# frames_v03.net
KiCad netlist of a schematic drawn in EAGLE
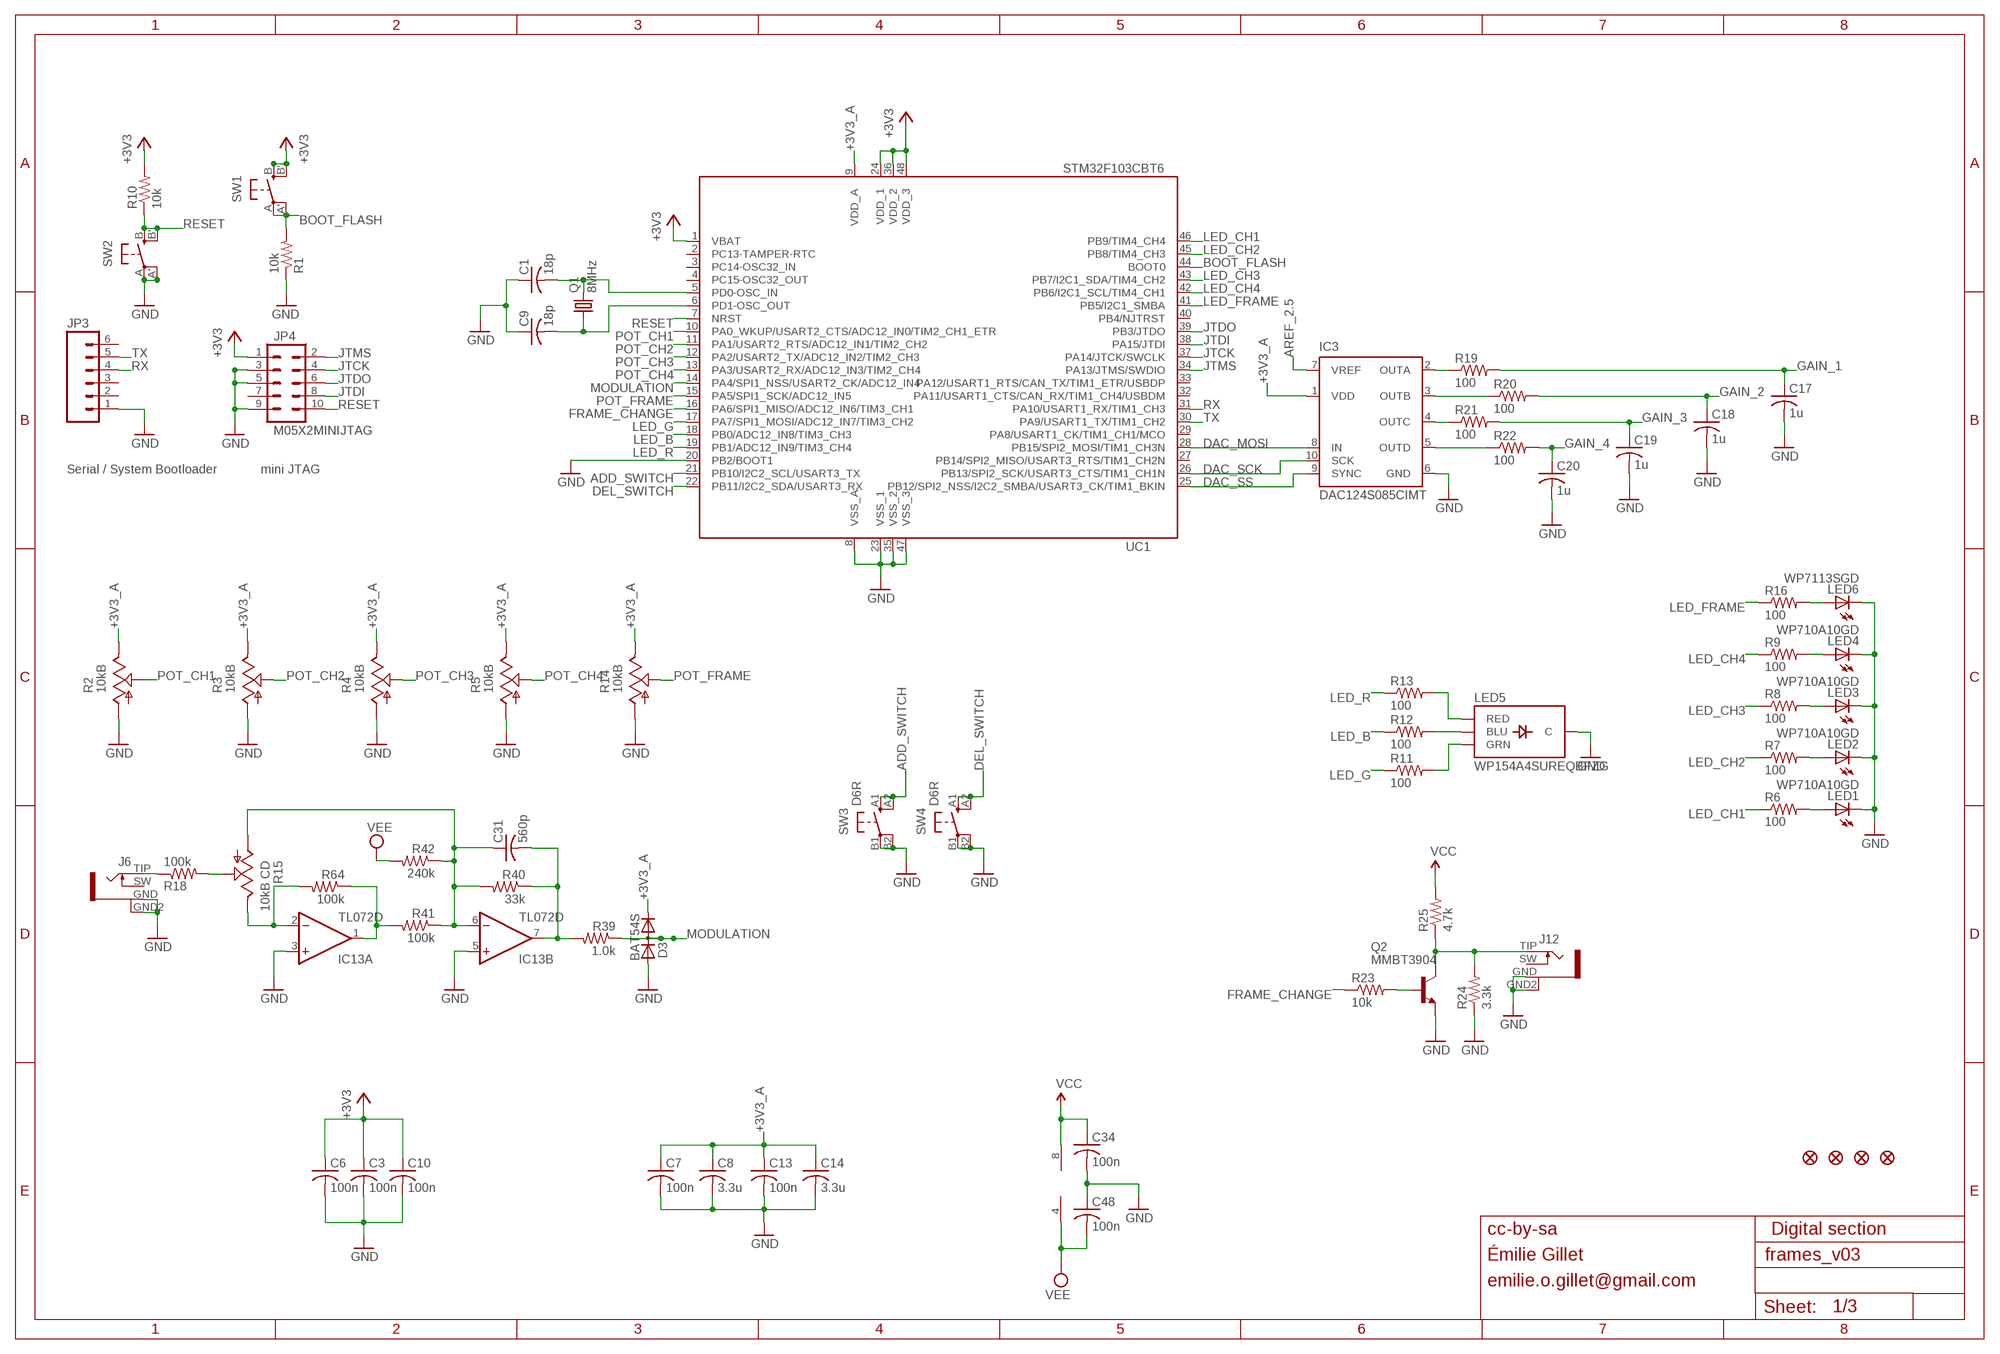
[diagram p0: schematic, sheet 1]
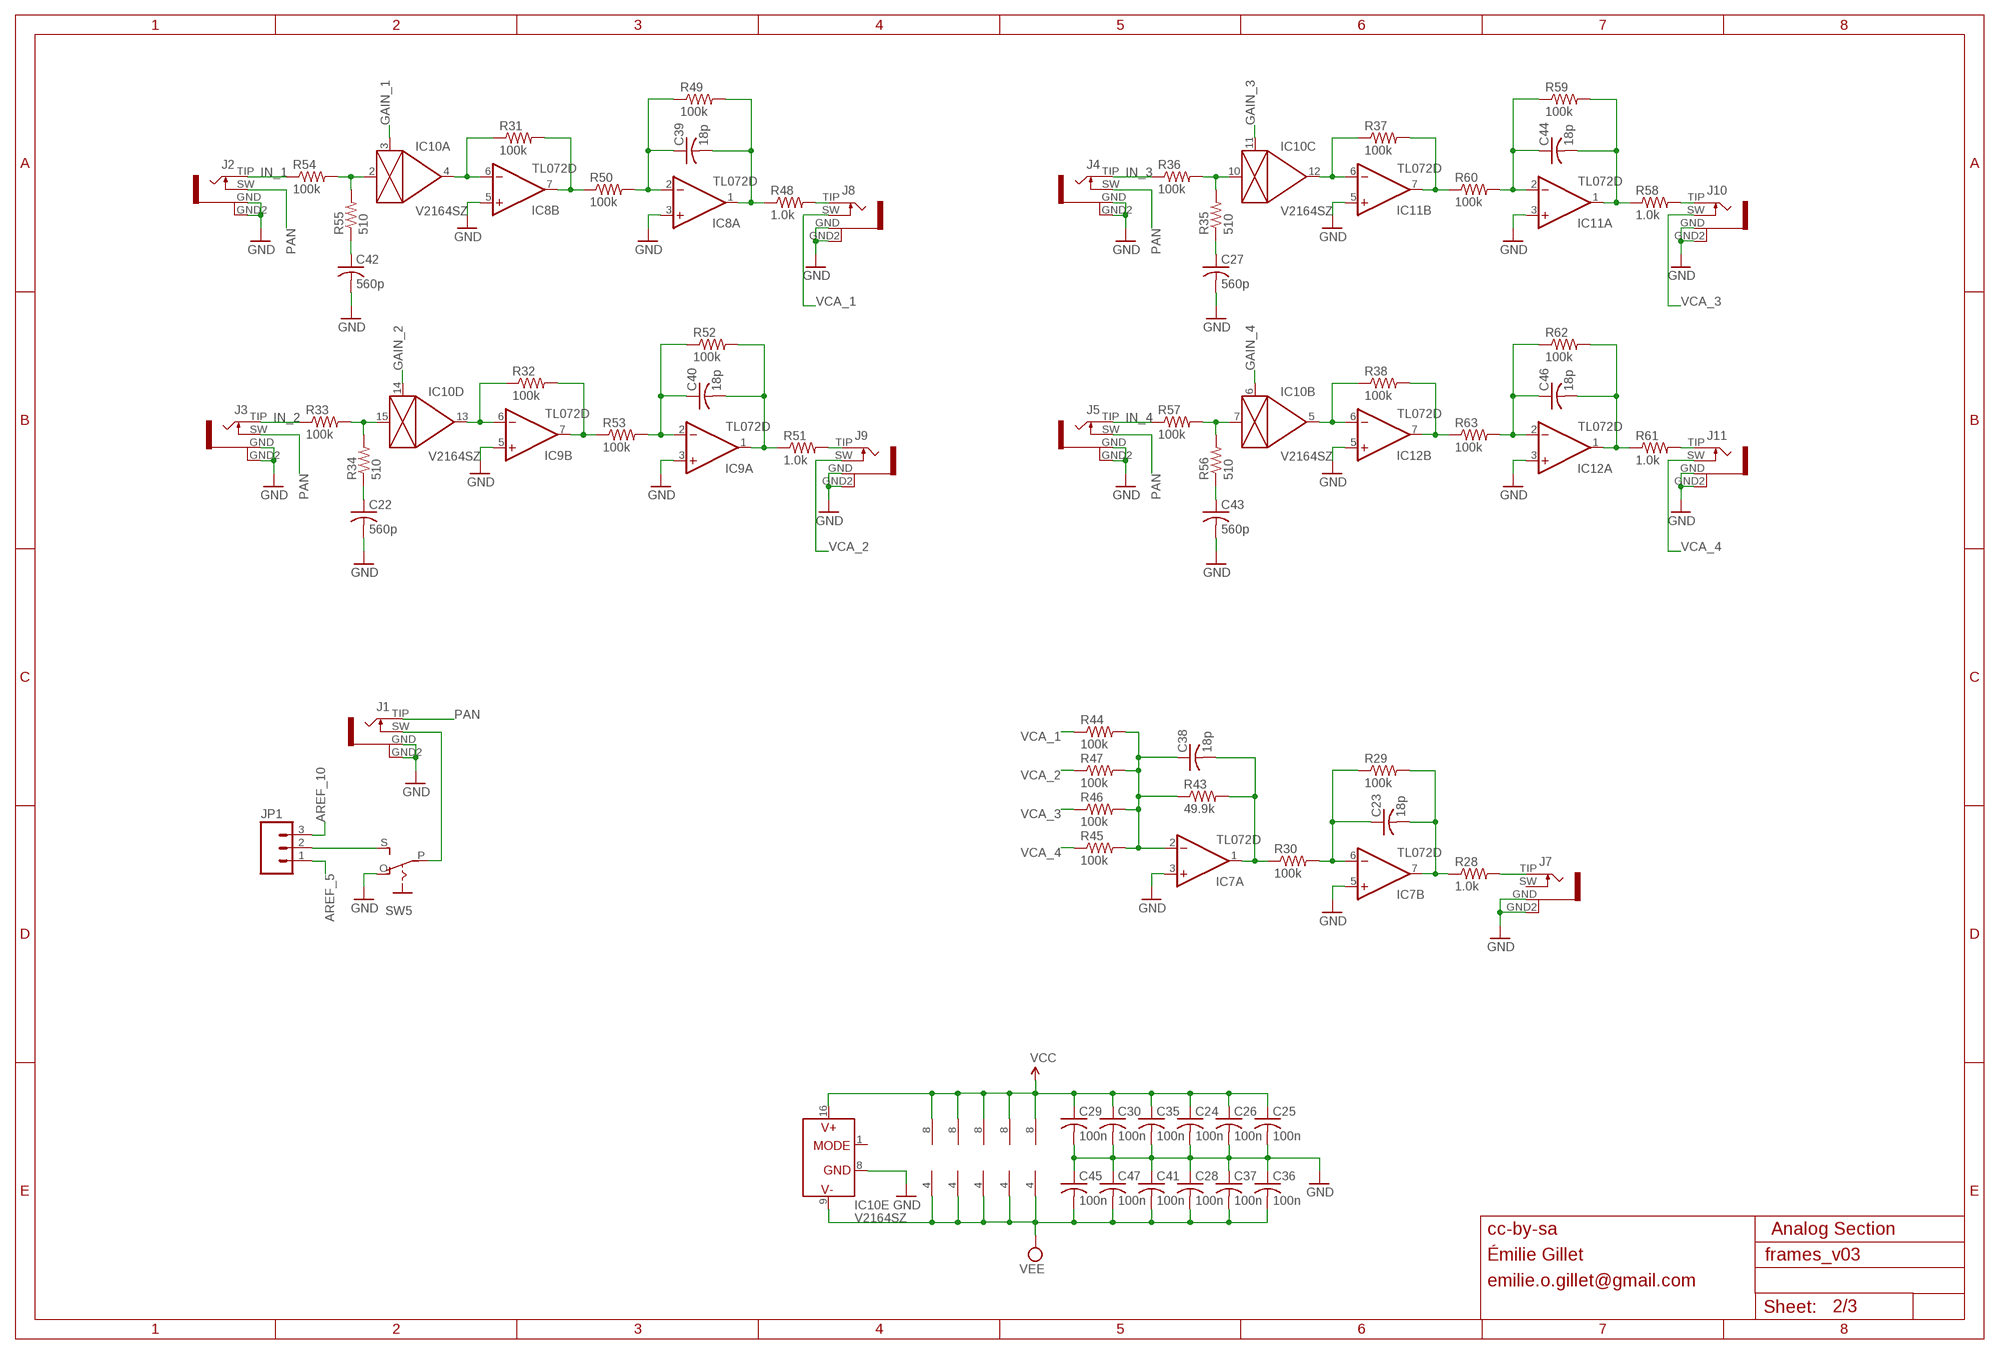
[diagram p1: schematic, sheet 2]
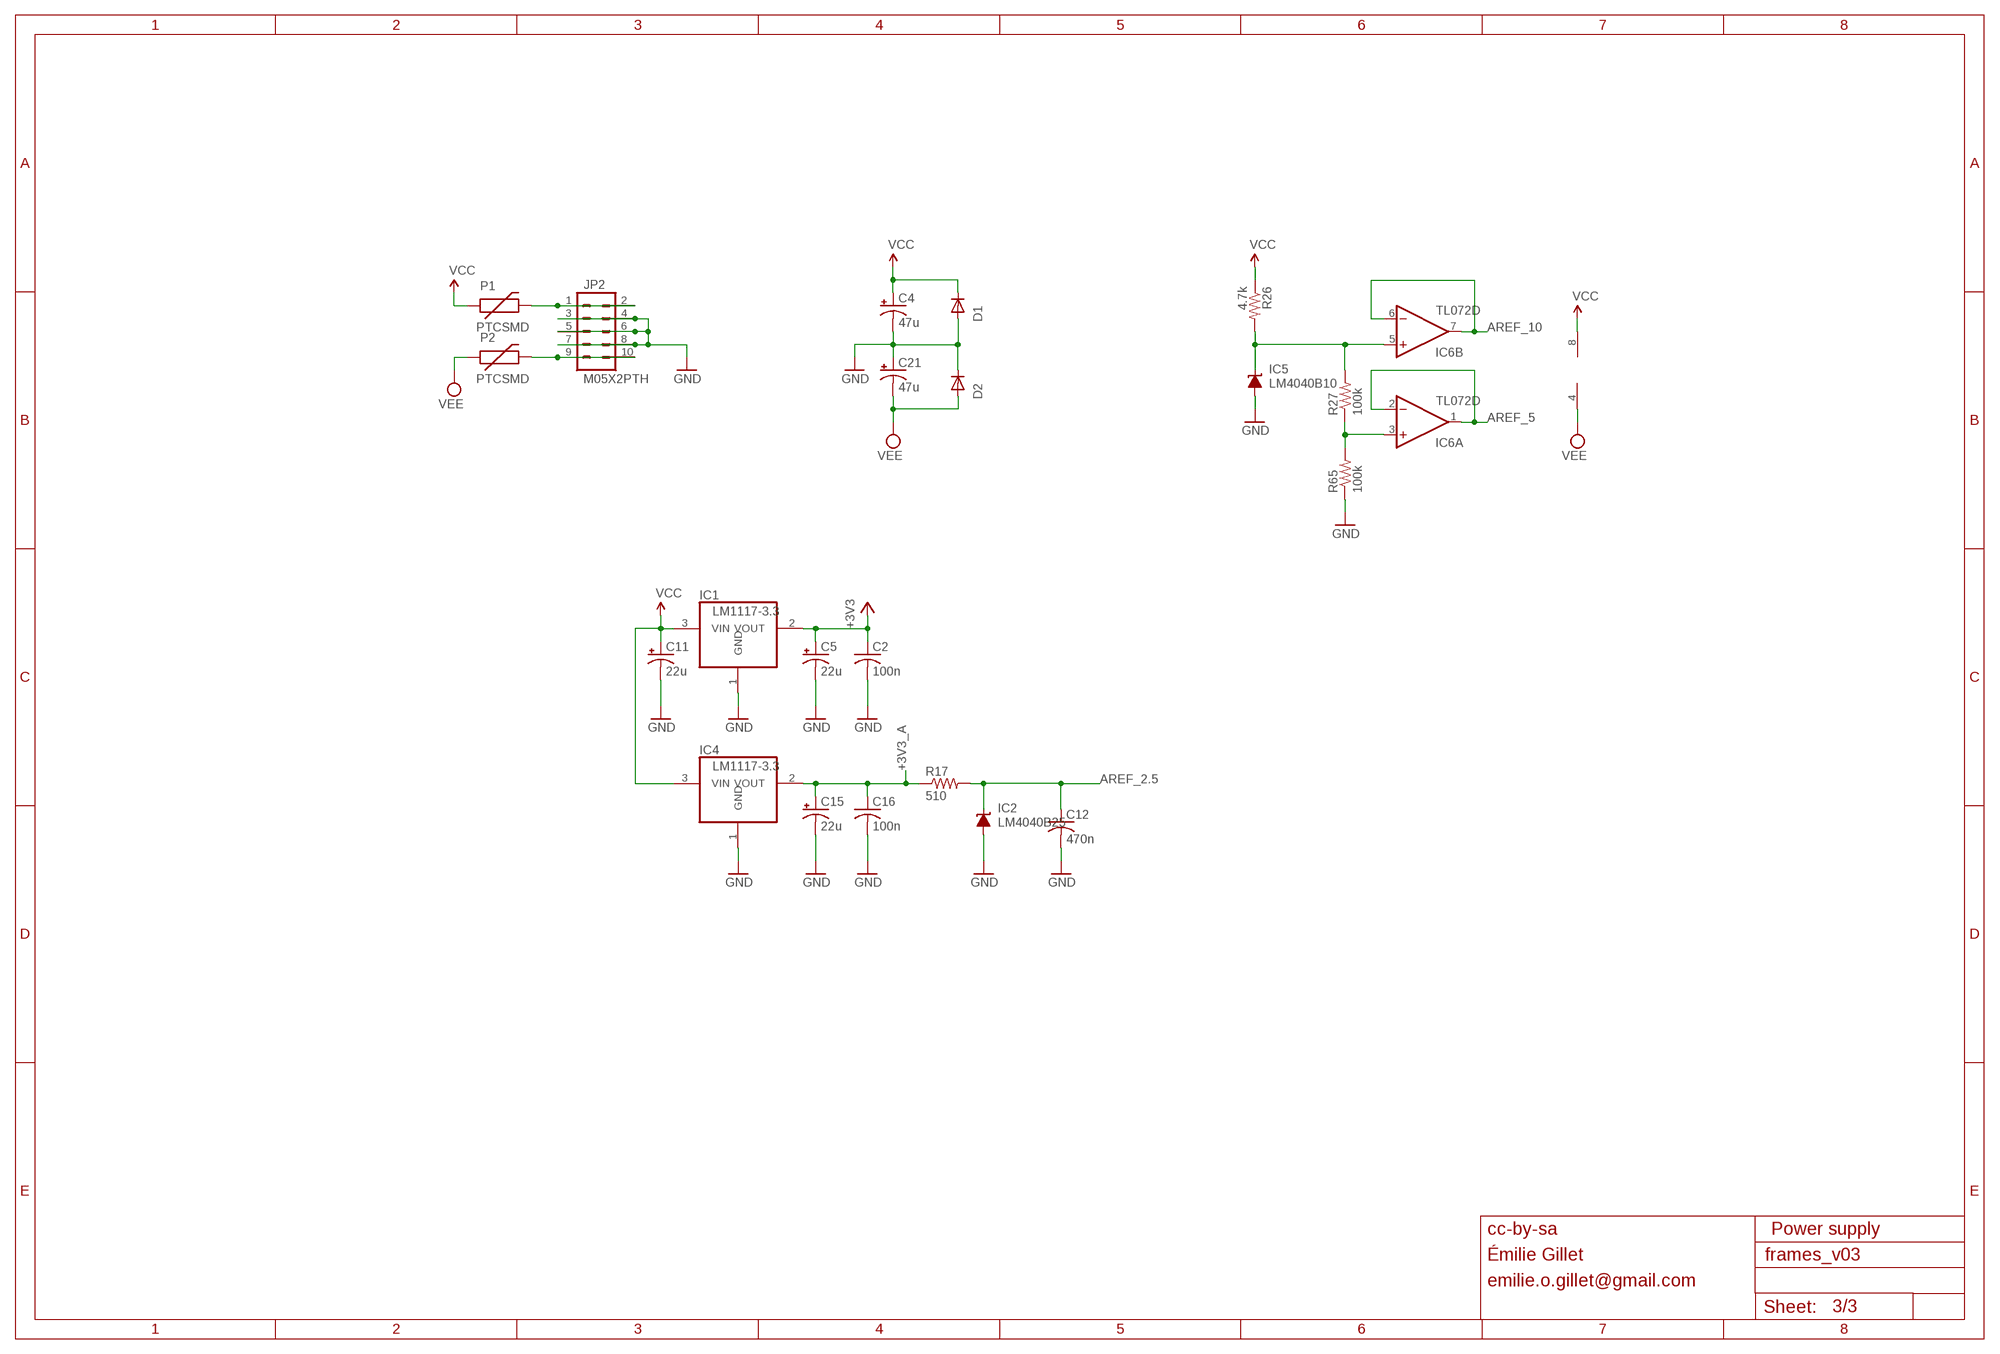
[diagram p2: schematic, sheet 3]

(export (version "E")
  (design (tool "Eeschema 10.0.6"))
  (components
    (comp (ref "C1")
      (value "18p")
      (footprint "eagle-import:C0603")
      (libsource (lib "eagle-import") (part "C-USC0603"))
    )
    (comp (ref "C3")
      (value "100n")
      (footprint "eagle-import:C0603")
      (libsource (lib "eagle-import") (part "C-USC0603"))
    )
    (comp (ref "C6")
      (value "100n")
      (footprint "eagle-import:C0603")
      (libsource (lib "eagle-import") (part "C-USC0603"))
    )
    (comp (ref "C7")
      (value "100n")
      (footprint "eagle-import:C0603")
      (libsource (lib "eagle-import") (part "C-USC0603"))
    )
    (comp (ref "C8")
      (value "3.3u")
      (footprint "eagle-import:C0603")
      (libsource (lib "eagle-import") (part "C-USC0603"))
    )
    (comp (ref "C9")
      (value "18p")
      (footprint "eagle-import:C0603")
      (libsource (lib "eagle-import") (part "C-USC0603"))
    )
    (comp (ref "C10")
      (value "100n")
      (footprint "eagle-import:C0603")
      (libsource (lib "eagle-import") (part "C-USC0603"))
    )
    (comp (ref "C13")
      (value "100n")
      (footprint "eagle-import:C0603")
      (libsource (lib "eagle-import") (part "C-USC0603"))
    )
    (comp (ref "C14")
      (value "3.3u")
      (footprint "eagle-import:C0603")
      (libsource (lib "eagle-import") (part "C-USC0603"))
    )
    (comp (ref "C17")
      (value "1u")
      (footprint "eagle-import:C0603")
      (libsource (lib "eagle-import") (part "C-USC0603"))
    )
    (comp (ref "C18")
      (value "1u")
      (footprint "eagle-import:C0603")
      (libsource (lib "eagle-import") (part "C-USC0603"))
    )
    (comp (ref "C19")
      (value "1u")
      (footprint "eagle-import:C0603")
      (libsource (lib "eagle-import") (part "C-USC0603"))
    )
    (comp (ref "C20")
      (value "1u")
      (footprint "eagle-import:C0603")
      (libsource (lib "eagle-import") (part "C-USC0603"))
    )
    (comp (ref "C31")
      (value "560p")
      (footprint "eagle-import:C0603")
      (libsource (lib "eagle-import") (part "C-USC0603"))
    )
    (comp (ref "C34")
      (value "100n")
      (footprint "eagle-import:C0603")
      (libsource (lib "eagle-import") (part "C-USC0603"))
    )
    (comp (ref "C48")
      (value "100n")
      (footprint "eagle-import:C0603")
      (libsource (lib "eagle-import") (part "C-USC0603"))
    )
    (comp (ref "D3")
      (value "BAT54S")
      (footprint "eagle-import:SOT23")
      (libsource (lib "eagle-import") (part "DIODE_2CACA-SOT23"))
    )
    (comp (ref "F1")
      (value "FIDUCIAL1X2")
      (footprint "eagle-import:FIDUCIAL-1X2")
      (libsource (lib "eagle-import") (part "FIDUCIAL1X2"))
    )
    (comp (ref "F2")
      (value "FIDUCIAL1X2")
      (footprint "eagle-import:FIDUCIAL-1X2")
      (libsource (lib "eagle-import") (part "FIDUCIAL1X2"))
    )
    (comp (ref "F3")
      (value "FIDUCIAL1X2")
      (footprint "eagle-import:FIDUCIAL-1X2")
      (libsource (lib "eagle-import") (part "FIDUCIAL1X2"))
    )
    (comp (ref "F4")
      (value "FIDUCIAL1X2")
      (footprint "eagle-import:FIDUCIAL-1X2")
      (libsource (lib "eagle-import") (part "FIDUCIAL1X2"))
    )
    (comp (ref "IC3")
      (value "DAC124S085CIMT")
      (footprint "eagle-import:MSOP10")
      (libsource (lib "eagle-import") (part "DAC124S085CIMT"))
    )
    (comp (ref "IC13")
      (value "TL072D")
      (footprint "eagle-import:SO08")
      (libsource (lib "eagle-import") (part "og-linear_TL072D"))
    )
    (comp (ref "J6")
      (value "PJ301WQP")
      (footprint "eagle-import:WQP_PJ_301BM")
      (libsource (lib "eagle-import") (part "PJ301WQP"))
    )
    (comp (ref "J12")
      (value "PJ301WQP")
      (footprint "eagle-import:WQP_PJ_301BM")
      (libsource (lib "eagle-import") (part "PJ301WQP"))
    )
    (comp (ref "JP3")
      (value "M06SIP")
      (footprint "eagle-import:1X06")
      (libsource (lib "eagle-import") (part "M06SIP"))
    )
    (comp (ref "JP4")
      (value "M05X2MINIJTAG")
      (footprint "eagle-import:2X5-1.27")
      (libsource (lib "eagle-import") (part "M05X2MINIJTAG"))
    )
    (comp (ref "LED1")
      (value "WP710A10GD")
      (footprint "eagle-import:LED3MM")
      (libsource (lib "eagle-import") (part "LED3MM"))
    )
    (comp (ref "LED2")
      (value "WP710A10GD")
      (footprint "eagle-import:LED3MM")
      (libsource (lib "eagle-import") (part "LED3MM"))
    )
    (comp (ref "LED3")
      (value "WP710A10GD")
      (footprint "eagle-import:LED3MM")
      (libsource (lib "eagle-import") (part "LED3MM"))
    )
    (comp (ref "LED4")
      (value "WP710A10GD")
      (footprint "eagle-import:LED3MM")
      (libsource (lib "eagle-import") (part "LED3MM"))
    )
    (comp (ref "LED5")
      (value "WP154A4SUREQBFZG")
      (footprint "eagle-import:LED-TRICOLOR-THROUGHHOLE")
      (libsource (lib "eagle-import") (part "LED-TRICOLOR-THROUGHHOLE"))
    )
    (comp (ref "LED6")
      (value "WP7113SGD")
      (footprint "eagle-import:LED5MM")
      (libsource (lib "eagle-import") (part "LED5MM"))
    )
    (comp (ref "Q1")
      (value "8MHz")
      (footprint "eagle-import:HC49UP")
      (libsource (lib "eagle-import") (part "CRYSTALHC49UP"))
    )
    (comp (ref "Q2")
      (value "MMBT3904")
      (footprint "eagle-import:SOT23-BEC")
      (libsource (lib "eagle-import") (part "-NPN-SOT23-BECMMBT3904LT1"))
    )
    (comp (ref "R1")
      (value "10k")
      (footprint "eagle-import:R0603")
      (libsource (lib "eagle-import") (part "R-US_R0603"))
    )
    (comp (ref "R2")
      (value "10kB")
      (footprint "eagle-import:ALPS_POT_VERTICAL_PS")
      (libsource (lib "eagle-import") (part "POT_USVERTICAL_PS"))
    )
    (comp (ref "R3")
      (value "10kB")
      (footprint "eagle-import:ALPS_POT_VERTICAL_PS")
      (libsource (lib "eagle-import") (part "POT_USVERTICAL_PS"))
    )
    (comp (ref "R4")
      (value "10kB")
      (footprint "eagle-import:ALPS_POT_VERTICAL_PS")
      (libsource (lib "eagle-import") (part "POT_USVERTICAL_PS"))
    )
    (comp (ref "R5")
      (value "10kB")
      (footprint "eagle-import:ALPS_POT_VERTICAL_PS")
      (libsource (lib "eagle-import") (part "POT_USVERTICAL_PS"))
    )
    (comp (ref "R6")
      (value "100")
      (footprint "eagle-import:R0603")
      (libsource (lib "eagle-import") (part "R-US_R0603"))
    )
    (comp (ref "R7")
      (value "100")
      (footprint "eagle-import:R0603")
      (libsource (lib "eagle-import") (part "R-US_R0603"))
    )
    (comp (ref "R8")
      (value "100")
      (footprint "eagle-import:R0603")
      (libsource (lib "eagle-import") (part "R-US_R0603"))
    )
    (comp (ref "R9")
      (value "100")
      (footprint "eagle-import:R0603")
      (libsource (lib "eagle-import") (part "R-US_R0603"))
    )
    (comp (ref "R10")
      (value "10k")
      (footprint "eagle-import:R0603")
      (libsource (lib "eagle-import") (part "R-US_R0603"))
    )
    (comp (ref "R11")
      (value "100")
      (footprint "eagle-import:R0603")
      (libsource (lib "eagle-import") (part "R-US_R0603"))
    )
    (comp (ref "R12")
      (value "100")
      (footprint "eagle-import:R0603")
      (libsource (lib "eagle-import") (part "R-US_R0603"))
    )
    (comp (ref "R13")
      (value "100")
      (footprint "eagle-import:R0603")
      (libsource (lib "eagle-import") (part "R-US_R0603"))
    )
    (comp (ref "R14")
      (value "10kB")
      (footprint "eagle-import:ALPS_POT_VERTICAL_PS")
      (libsource (lib "eagle-import") (part "POT_USVERTICAL_PS"))
    )
    (comp (ref "R15")
      (value "10kB CD")
      (footprint "eagle-import:ALPS_POT_VERTICAL_PS")
      (libsource (lib "eagle-import") (part "POT_USVERTICAL_PS"))
    )
    (comp (ref "R16")
      (value "100")
      (footprint "eagle-import:R0603")
      (libsource (lib "eagle-import") (part "R-US_R0603"))
    )
    (comp (ref "R18")
      (value "100k")
      (footprint "eagle-import:R0603")
      (libsource (lib "eagle-import") (part "R-US_R0603"))
    )
    (comp (ref "R19")
      (value "100")
      (footprint "eagle-import:R0603")
      (libsource (lib "eagle-import") (part "R-US_R0603"))
    )
    (comp (ref "R20")
      (value "100")
      (footprint "eagle-import:R0603")
      (libsource (lib "eagle-import") (part "R-US_R0603"))
    )
    (comp (ref "R21")
      (value "100")
      (footprint "eagle-import:R0603")
      (libsource (lib "eagle-import") (part "R-US_R0603"))
    )
    (comp (ref "R22")
      (value "100")
      (footprint "eagle-import:R0603")
      (libsource (lib "eagle-import") (part "R-US_R0603"))
    )
    (comp (ref "R23")
      (value "10k")
      (footprint "eagle-import:R0603")
      (libsource (lib "eagle-import") (part "R-US_R0603"))
    )
    (comp (ref "R24")
      (value "3.3k")
      (footprint "eagle-import:R0603")
      (libsource (lib "eagle-import") (part "R-US_R0603"))
    )
    (comp (ref "R25")
      (value "4.7k")
      (footprint "eagle-import:R0603")
      (libsource (lib "eagle-import") (part "R-US_R0603"))
    )
    (comp (ref "R39")
      (value "1.0k")
      (footprint "eagle-import:R0603")
      (libsource (lib "eagle-import") (part "R-US_R0603"))
    )
    (comp (ref "R40")
      (value "33k")
      (footprint "eagle-import:R0603")
      (libsource (lib "eagle-import") (part "R-US_R0603"))
    )
    (comp (ref "R41")
      (value "100k")
      (footprint "eagle-import:R0603")
      (libsource (lib "eagle-import") (part "R-US_R0603"))
    )
    (comp (ref "R42")
      (value "240k")
      (footprint "eagle-import:R0603")
      (libsource (lib "eagle-import") (part "R-US_R0603"))
    )
    (comp (ref "R64")
      (value "100k")
      (footprint "eagle-import:R0603")
      (libsource (lib "eagle-import") (part "R-US_R0603"))
    )
    (comp (ref "SW1")
      (value "EVQQ2")
      (footprint "eagle-import:EVQ-Q2")
      (libsource (lib "eagle-import") (part "EVQQ2"))
    )
    (comp (ref "SW2")
      (value "EVQQ2")
      (footprint "eagle-import:EVQ-Q2")
      (libsource (lib "eagle-import") (part "EVQQ2"))
    )
    (comp (ref "SW3")
      (value "D6R")
      (footprint "eagle-import:D6R")
      (libsource (lib "eagle-import") (part "D6R"))
    )
    (comp (ref "SW4")
      (value "D6R")
      (footprint "eagle-import:D6R")
      (libsource (lib "eagle-import") (part "D6R"))
    )
    (comp (ref "UC1")
      (value "STM32F103CBT6")
      (footprint "eagle-import:LQFP48")
      (libsource (lib "eagle-import") (part "STM32F103CB"))
    )
    (comp (ref "C22")
      (value "560p")
      (footprint "eagle-import:C0603")
      (libsource (lib "eagle-import") (part "C-USC0603"))
    )
    (comp (ref "C23")
      (value "18p")
      (footprint "eagle-import:C0603")
      (libsource (lib "eagle-import") (part "C-USC0603"))
    )
    (comp (ref "C24")
      (value "100n")
      (footprint "eagle-import:C0603")
      (libsource (lib "eagle-import") (part "C-USC0603"))
    )
    (comp (ref "C25")
      (value "100n")
      (footprint "eagle-import:C0603")
      (libsource (lib "eagle-import") (part "C-USC0603"))
    )
    (comp (ref "C26")
      (value "100n")
      (footprint "eagle-import:C0603")
      (libsource (lib "eagle-import") (part "C-USC0603"))
    )
    (comp (ref "C27")
      (value "560p")
      (footprint "eagle-import:C0603")
      (libsource (lib "eagle-import") (part "C-USC0603"))
    )
    (comp (ref "C28")
      (value "100n")
      (footprint "eagle-import:C0603")
      (libsource (lib "eagle-import") (part "C-USC0603"))
    )
    (comp (ref "C29")
      (value "100n")
      (footprint "eagle-import:C0603")
      (libsource (lib "eagle-import") (part "C-USC0603"))
    )
    (comp (ref "C30")
      (value "100n")
      (footprint "eagle-import:C0603")
      (libsource (lib "eagle-import") (part "C-USC0603"))
    )
    (comp (ref "C35")
      (value "100n")
      (footprint "eagle-import:C0603")
      (libsource (lib "eagle-import") (part "C-USC0603"))
    )
    (comp (ref "C36")
      (value "100n")
      (footprint "eagle-import:C0603")
      (libsource (lib "eagle-import") (part "C-USC0603"))
    )
    (comp (ref "C37")
      (value "100n")
      (footprint "eagle-import:C0603")
      (libsource (lib "eagle-import") (part "C-USC0603"))
    )
    (comp (ref "C38")
      (value "18p")
      (footprint "eagle-import:C0603")
      (libsource (lib "eagle-import") (part "C-USC0603"))
    )
    (comp (ref "C39")
      (value "18p")
      (footprint "eagle-import:C0603")
      (libsource (lib "eagle-import") (part "C-USC0603"))
    )
    (comp (ref "C40")
      (value "18p")
      (footprint "eagle-import:C0603")
      (libsource (lib "eagle-import") (part "C-USC0603"))
    )
    (comp (ref "C41")
      (value "100n")
      (footprint "eagle-import:C0603")
      (libsource (lib "eagle-import") (part "C-USC0603"))
    )
    (comp (ref "C42")
      (value "560p")
      (footprint "eagle-import:C0603")
      (libsource (lib "eagle-import") (part "C-USC0603"))
    )
    (comp (ref "C43")
      (value "560p")
      (footprint "eagle-import:C0603")
      (libsource (lib "eagle-import") (part "C-USC0603"))
    )
    (comp (ref "C44")
      (value "18p")
      (footprint "eagle-import:C0603")
      (libsource (lib "eagle-import") (part "C-USC0603"))
    )
    (comp (ref "C45")
      (value "100n")
      (footprint "eagle-import:C0603")
      (libsource (lib "eagle-import") (part "C-USC0603"))
    )
    (comp (ref "C46")
      (value "18p")
      (footprint "eagle-import:C0603")
      (libsource (lib "eagle-import") (part "C-USC0603"))
    )
    (comp (ref "C47")
      (value "100n")
      (footprint "eagle-import:C0603")
      (libsource (lib "eagle-import") (part "C-USC0603"))
    )
    (comp (ref "IC7")
      (value "TL072D")
      (footprint "eagle-import:SO08")
      (libsource (lib "eagle-import") (part "og-linear_TL072D"))
    )
    (comp (ref "IC8")
      (value "TL072D")
      (footprint "eagle-import:SO08")
      (libsource (lib "eagle-import") (part "og-linear_TL072D"))
    )
    (comp (ref "IC9")
      (value "TL072D")
      (footprint "eagle-import:SO08")
      (libsource (lib "eagle-import") (part "og-linear_TL072D"))
    )
    (comp (ref "IC10")
      (value "V2164SZ")
      (footprint "eagle-import:SOIC16N")
      (libsource (lib "eagle-import") (part "SSM2164S"))
    )
    (comp (ref "IC11")
      (value "TL072D")
      (footprint "eagle-import:SO08")
      (libsource (lib "eagle-import") (part "og-linear_TL072D"))
    )
    (comp (ref "IC12")
      (value "TL072D")
      (footprint "eagle-import:SO08")
      (libsource (lib "eagle-import") (part "og-linear_TL072D"))
    )
    (comp (ref "J1")
      (value "PJ301WQP")
      (footprint "eagle-import:WQP_PJ_301BM")
      (libsource (lib "eagle-import") (part "PJ301WQP"))
    )
    (comp (ref "J2")
      (value "PJ301WQP")
      (footprint "eagle-import:WQP_PJ_301BM")
      (libsource (lib "eagle-import") (part "PJ301WQP"))
    )
    (comp (ref "J3")
      (value "PJ301WQP")
      (footprint "eagle-import:WQP_PJ_301BM")
      (libsource (lib "eagle-import") (part "PJ301WQP"))
    )
    (comp (ref "J4")
      (value "PJ301WQP")
      (footprint "eagle-import:WQP_PJ_301BM")
      (libsource (lib "eagle-import") (part "PJ301WQP"))
    )
    (comp (ref "J5")
      (value "PJ301WQP")
      (footprint "eagle-import:WQP_PJ_301BM")
      (libsource (lib "eagle-import") (part "PJ301WQP"))
    )
    (comp (ref "J7")
      (value "PJ301WQP")
      (footprint "eagle-import:WQP_PJ_301BM")
      (libsource (lib "eagle-import") (part "PJ301WQP"))
    )
    (comp (ref "J8")
      (value "PJ301WQP")
      (footprint "eagle-import:WQP_PJ_301BM")
      (libsource (lib "eagle-import") (part "PJ301WQP"))
    )
    (comp (ref "J9")
      (value "PJ301WQP")
      (footprint "eagle-import:WQP_PJ_301BM")
      (libsource (lib "eagle-import") (part "PJ301WQP"))
    )
    (comp (ref "J10")
      (value "PJ301WQP")
      (footprint "eagle-import:WQP_PJ_301BM")
      (libsource (lib "eagle-import") (part "PJ301WQP"))
    )
    (comp (ref "J11")
      (value "PJ301WQP")
      (footprint "eagle-import:WQP_PJ_301BM")
      (libsource (lib "eagle-import") (part "PJ301WQP"))
    )
    (comp (ref "JP1")
      (value "M03PTH")
      (footprint "eagle-import:1X03")
      (libsource (lib "eagle-import") (part "M03PTH"))
    )
    (comp (ref "R28")
      (value "1.0k")
      (footprint "eagle-import:R0603")
      (libsource (lib "eagle-import") (part "R-US_R0603"))
    )
    (comp (ref "R29")
      (value "100k")
      (footprint "eagle-import:R0603")
      (libsource (lib "eagle-import") (part "R-US_R0603"))
    )
    (comp (ref "R30")
      (value "100k")
      (footprint "eagle-import:R0603")
      (libsource (lib "eagle-import") (part "R-US_R0603"))
    )
    (comp (ref "R31")
      (value "100k")
      (footprint "eagle-import:R0603")
      (libsource (lib "eagle-import") (part "R-US_R0603"))
    )
    (comp (ref "R32")
      (value "100k")
      (footprint "eagle-import:R0603")
      (libsource (lib "eagle-import") (part "R-US_R0603"))
    )
    (comp (ref "R33")
      (value "100k")
      (footprint "eagle-import:R0603")
      (libsource (lib "eagle-import") (part "R-US_R0603"))
    )
    (comp (ref "R34")
      (value "510")
      (footprint "eagle-import:R0603")
      (libsource (lib "eagle-import") (part "R-US_R0603"))
    )
    (comp (ref "R35")
      (value "510")
      (footprint "eagle-import:R0603")
      (libsource (lib "eagle-import") (part "R-US_R0603"))
    )
    (comp (ref "R36")
      (value "100k")
      (footprint "eagle-import:R0603")
      (libsource (lib "eagle-import") (part "R-US_R0603"))
    )
    (comp (ref "R37")
      (value "100k")
      (footprint "eagle-import:R0603")
      (libsource (lib "eagle-import") (part "R-US_R0603"))
    )
    (comp (ref "R38")
      (value "100k")
      (footprint "eagle-import:R0603")
      (libsource (lib "eagle-import") (part "R-US_R0603"))
    )
    (comp (ref "R43")
      (value "49.9k")
      (footprint "eagle-import:R0603")
      (libsource (lib "eagle-import") (part "R-US_R0603"))
    )
    (comp (ref "R44")
      (value "100k")
      (footprint "eagle-import:R0603")
      (libsource (lib "eagle-import") (part "R-US_R0603"))
    )
    (comp (ref "R45")
      (value "100k")
      (footprint "eagle-import:R0603")
      (libsource (lib "eagle-import") (part "R-US_R0603"))
    )
    (comp (ref "R46")
      (value "100k")
      (footprint "eagle-import:R0603")
      (libsource (lib "eagle-import") (part "R-US_R0603"))
    )
    (comp (ref "R47")
      (value "100k")
      (footprint "eagle-import:R0603")
      (libsource (lib "eagle-import") (part "R-US_R0603"))
    )
    (comp (ref "R48")
      (value "1.0k")
      (footprint "eagle-import:R0603")
      (libsource (lib "eagle-import") (part "R-US_R0603"))
    )
    (comp (ref "R49")
      (value "100k")
      (footprint "eagle-import:R0603")
      (libsource (lib "eagle-import") (part "R-US_R0603"))
    )
    (comp (ref "R50")
      (value "100k")
      (footprint "eagle-import:R0603")
      (libsource (lib "eagle-import") (part "R-US_R0603"))
    )
    (comp (ref "R51")
      (value "1.0k")
      (footprint "eagle-import:R0603")
      (libsource (lib "eagle-import") (part "R-US_R0603"))
    )
    (comp (ref "R52")
      (value "100k")
      (footprint "eagle-import:R0603")
      (libsource (lib "eagle-import") (part "R-US_R0603"))
    )
    (comp (ref "R53")
      (value "100k")
      (footprint "eagle-import:R0603")
      (libsource (lib "eagle-import") (part "R-US_R0603"))
    )
    (comp (ref "R54")
      (value "100k")
      (footprint "eagle-import:R0603")
      (libsource (lib "eagle-import") (part "R-US_R0603"))
    )
    (comp (ref "R55")
      (value "510")
      (footprint "eagle-import:R0603")
      (libsource (lib "eagle-import") (part "R-US_R0603"))
    )
    (comp (ref "R56")
      (value "510")
      (footprint "eagle-import:R0603")
      (libsource (lib "eagle-import") (part "R-US_R0603"))
    )
    (comp (ref "R57")
      (value "100k")
      (footprint "eagle-import:R0603")
      (libsource (lib "eagle-import") (part "R-US_R0603"))
    )
    (comp (ref "R58")
      (value "1.0k")
      (footprint "eagle-import:R0603")
      (libsource (lib "eagle-import") (part "R-US_R0603"))
    )
    (comp (ref "R59")
      (value "100k")
      (footprint "eagle-import:R0603")
      (libsource (lib "eagle-import") (part "R-US_R0603"))
    )
    (comp (ref "R60")
      (value "100k")
      (footprint "eagle-import:R0603")
      (libsource (lib "eagle-import") (part "R-US_R0603"))
    )
    (comp (ref "R61")
      (value "1.0k")
      (footprint "eagle-import:R0603")
      (libsource (lib "eagle-import") (part "R-US_R0603"))
    )
    (comp (ref "R62")
      (value "100k")
      (footprint "eagle-import:R0603")
      (libsource (lib "eagle-import") (part "R-US_R0603"))
    )
    (comp (ref "R63")
      (value "100k")
      (footprint "eagle-import:R0603")
      (libsource (lib "eagle-import") (part "R-US_R0603"))
    )
    (comp (ref "SW5")
      (value "S-ON-ONSMALL_SLIDE")
      (footprint "eagle-import:ES_100SP1T6B11M2QEH_SMALL")
      (libsource (lib "eagle-import") (part "S-ON-ONSMALL_SLIDE"))
    )
    (comp (ref "C2")
      (value "100n")
      (footprint "eagle-import:C0603")
      (libsource (lib "eagle-import") (part "C-USC0603"))
    )
    (comp (ref "C4")
      (value "47u")
      (footprint "eagle-import:PANASONIC_D")
      (libsource (lib "eagle-import") (part "CPOL-USD"))
    )
    (comp (ref "C5")
      (value "22u")
      (footprint "eagle-import:PANASONIC_C")
      (libsource (lib "eagle-import") (part "CPOL-USC"))
    )
    (comp (ref "C11")
      (value "22u")
      (footprint "eagle-import:PANASONIC_C")
      (libsource (lib "eagle-import") (part "CPOL-USC"))
    )
    (comp (ref "C12")
      (value "470n")
      (footprint "eagle-import:C0603")
      (libsource (lib "eagle-import") (part "C-USC0603"))
    )
    (comp (ref "C15")
      (value "22u")
      (footprint "eagle-import:PANASONIC_C")
      (libsource (lib "eagle-import") (part "CPOL-USC"))
    )
    (comp (ref "C16")
      (value "100n")
      (footprint "eagle-import:C0603")
      (libsource (lib "eagle-import") (part "C-USC0603"))
    )
    (comp (ref "C21")
      (value "47u")
      (footprint "eagle-import:PANASONIC_D")
      (libsource (lib "eagle-import") (part "CPOL-USD"))
    )
    (comp (ref "D1")
      (value "1N5819HW")
      (footprint "eagle-import:SOD123")
      (libsource (lib "eagle-import") (part "DIODE-SOD123"))
    )
    (comp (ref "D2")
      (value "1N5819HW")
      (footprint "eagle-import:SOD123")
      (libsource (lib "eagle-import") (part "DIODE-SOD123"))
    )
    (comp (ref "IC1")
      (value "LM1117-3.3")
      (footprint "eagle-import:SOT223")
      (libsource (lib "eagle-import") (part "REG1117"))
    )
    (comp (ref "IC2")
      (value "LM4040B25")
      (footprint "eagle-import:DBZ_R-PDSO-G3")
      (libsource (lib "eagle-import") (part "LM4041DBZB12"))
    )
    (comp (ref "IC4")
      (value "LM1117-3.3")
      (footprint "eagle-import:SOT223")
      (libsource (lib "eagle-import") (part "REG1117"))
    )
    (comp (ref "IC5")
      (value "LM4040B10")
      (footprint "eagle-import:DBZ_R-PDSO-G3")
      (libsource (lib "eagle-import") (part "LM4041DBZB12"))
    )
    (comp (ref "IC6")
      (value "TL072D")
      (footprint "eagle-import:SO08")
      (libsource (lib "eagle-import") (part "TL072D"))
    )
    (comp (ref "JP2")
      (value "M05X2PTH")
      (footprint "eagle-import:AVR_ICSP")
      (libsource (lib "eagle-import") (part "M05X2PTH"))
    )
    (comp (ref "P1")
      (value "PTCSMD")
      (footprint "eagle-import:PTC-1206")
      (libsource (lib "eagle-import") (part "PTCSMD"))
    )
    (comp (ref "P2")
      (value "PTCSMD")
      (footprint "eagle-import:PTC-1206")
      (libsource (lib "eagle-import") (part "PTCSMD"))
    )
    (comp (ref "R17")
      (value "510")
      (footprint "eagle-import:R0603")
      (libsource (lib "eagle-import") (part "R-US_R0603"))
    )
    (comp (ref "R26")
      (value "4.7k")
      (footprint "eagle-import:R0603")
      (libsource (lib "eagle-import") (part "R-US_R0603"))
    )
    (comp (ref "R27")
      (value "100k")
      (footprint "eagle-import:R0603")
      (libsource (lib "eagle-import") (part "R-US_R0603"))
    )
    (comp (ref "R65")
      (value "100k")
      (footprint "eagle-import:R0603")
      (libsource (lib "eagle-import") (part "R-US_R0603"))
    )
  )
  (nets
    (net (code "1") (name "+3V3") (class "Default")
      (node (ref "C10") (pin "1") (pinfunction "1_1") (pintype "passive"))
      (node (ref "C2") (pin "1") (pinfunction "1_1") (pintype "passive"))
      (node (ref "C3") (pin "1") (pinfunction "1_1") (pintype "passive"))
      (node (ref "C5") (pin "+") (pinfunction "+_+") (pintype "passive"))
      (node (ref "C6") (pin "1") (pinfunction "1_1") (pintype "passive"))
      (node (ref "IC1") (pin "2") (pinfunction "VOUT_2") (pintype "output"))
      (node (ref "JP4") (pin "1") (pinfunction "1_1") (pintype "passive"))
      (node (ref "R10") (pin "2") (pinfunction "2_2") (pintype "passive"))
      (node (ref "SW1") (pin "B") (pinfunction "S_B") (pintype "passive"))
      (node (ref "SW1") (pin "B'") (pinfunction "S1_B'") (pintype "passive"))
      (node (ref "UC1") (pin "1") (pinfunction "VBAT_1") (pintype "power_in"))
      (node (ref "UC1") (pin "24") (pinfunction "VDD_1_24") (pintype "power_in"))
      (node (ref "UC1") (pin "36") (pinfunction "VDD_2_36") (pintype "power_in"))
      (node (ref "UC1") (pin "48") (pinfunction "VDD_3_48") (pintype "power_in"))
    )
    (net (code "2") (name "+3V3_A") (class "Default")
      (node (ref "C13") (pin "1") (pinfunction "1_1") (pintype "passive"))
      (node (ref "C14") (pin "1") (pinfunction "1_1") (pintype "passive"))
      (node (ref "C15") (pin "+") (pinfunction "+_+") (pintype "passive"))
      (node (ref "C16") (pin "1") (pinfunction "1_1") (pintype "passive"))
      (node (ref "C7") (pin "1") (pinfunction "1_1") (pintype "passive"))
      (node (ref "C8") (pin "1") (pinfunction "1_1") (pintype "passive"))
      (node (ref "D3") (pin "2") (pinfunction "C_2") (pintype "passive"))
      (node (ref "IC3") (pin "1") (pinfunction "VDD_1") (pintype "power_in"))
      (node (ref "IC4") (pin "2") (pinfunction "VOUT_2") (pintype "output"))
      (node (ref "R14") (pin "P$1") (pinfunction "E_P$1") (pintype "passive"))
      (node (ref "R17") (pin "1") (pinfunction "1_1") (pintype "passive"))
      (node (ref "R2") (pin "P$1") (pinfunction "E_P$1") (pintype "passive"))
      (node (ref "R3") (pin "P$1") (pinfunction "E_P$1") (pintype "passive"))
      (node (ref "R4") (pin "P$1") (pinfunction "E_P$1") (pintype "passive"))
      (node (ref "R5") (pin "P$1") (pinfunction "E_P$1") (pintype "passive"))
      (node (ref "UC1") (pin "9") (pinfunction "VDD_A_9") (pintype "power_in"))
    )
    (net (code "3") (name "ADD_SWITCH") (class "Default")
      (node (ref "SW3") (pin "A1") (pinfunction "S_A1") (pintype "passive"))
      (node (ref "SW3") (pin "A2") (pinfunction "S1_A2") (pintype "passive"))
      (node (ref "UC1") (pin "21") (pinfunction "PB10/I2C2_SCL/USART3_TX_21") (pintype "input"))
    )
    (net (code "4") (name "AREF_2.5") (class "Default")
      (node (ref "C12") (pin "1") (pinfunction "1_1") (pintype "passive"))
      (node (ref "IC2") (pin "1") (pinfunction "C_1") (pintype "passive"))
      (node (ref "IC3") (pin "7") (pinfunction "VREF_7") (pintype "bidirectional"))
      (node (ref "R17") (pin "2") (pinfunction "2_2") (pintype "passive"))
    )
    (net (code "5") (name "AREF_5") (class "Default")
      (node (ref "IC6") (pin "1") (pinfunction "OUT_1") (pintype "output"))
      (node (ref "IC6") (pin "2") (pinfunction "-IN_2") (pintype "input"))
      (node (ref "JP1") (pin "1") (pinfunction "1_1") (pintype "passive"))
    )
    (net (code "6") (name "AREF_10") (class "Default")
      (node (ref "IC6") (pin "6") (pinfunction "-IN_6") (pintype "input"))
      (node (ref "IC6") (pin "7") (pinfunction "OUT_7") (pintype "output"))
      (node (ref "JP1") (pin "3") (pinfunction "3_3") (pintype "passive"))
    )
    (net (code "7") (name "BOOT_FLASH") (class "Default")
      (node (ref "R1") (pin "2") (pinfunction "2_2") (pintype "passive"))
      (node (ref "SW1") (pin "A") (pinfunction "P_A") (pintype "passive"))
      (node (ref "SW1") (pin "A'") (pinfunction "P1_A'") (pintype "passive"))
      (node (ref "UC1") (pin "44") (pinfunction "BOOT0_44") (pintype "input"))
    )
    (net (code "8") (name "DAC_MOSI") (class "Default")
      (node (ref "IC3") (pin "8") (pinfunction "IN_8") (pintype "input"))
      (node (ref "UC1") (pin "28") (pinfunction "PB15/SPI2_MOSI/TIM1_CH3N_28") (pintype "input"))
    )
    (net (code "9") (name "DAC_SCK") (class "Default")
      (node (ref "IC3") (pin "10") (pinfunction "SCK_10") (pintype "input"))
      (node (ref "UC1") (pin "26") (pinfunction "PB13/SPI2_SCK/USART3_CTS/TIM1_CH1N_26") (pintype "input"))
    )
    (net (code "10") (name "DAC_SS") (class "Default")
      (node (ref "IC3") (pin "9") (pinfunction "SYNC_9") (pintype "input"))
      (node (ref "UC1") (pin "25") (pinfunction "PB12/SPI2_NSS/I2C2_SMBA/USART3_CK/TIM1_BKIN_25") (pintype "input"))
    )
    (net (code "11") (name "DEL_SWITCH") (class "Default")
      (node (ref "SW4") (pin "A1") (pinfunction "S_A1") (pintype "passive"))
      (node (ref "SW4") (pin "A2") (pinfunction "S1_A2") (pintype "passive"))
      (node (ref "UC1") (pin "22") (pinfunction "PB11/I2C2_SDA/USART3_RX_22") (pintype "input"))
    )
    (net (code "12") (name "FRAME_CHANGE") (class "Default")
      (node (ref "R23") (pin "1") (pinfunction "1_1") (pintype "passive"))
      (node (ref "UC1") (pin "16") (pinfunction "PA6/SPI1_MISO/ADC12_IN6/TIM3_CH1_16") (pintype "bidirectional"))
    )
    (net (code "13") (name "GAIN_1") (class "Default")
      (node (ref "C17") (pin "1") (pinfunction "1_1") (pintype "passive"))
      (node (ref "IC10") (pin "3") (pinfunction "CTRL_3") (pintype "input"))
      (node (ref "R19") (pin "2") (pinfunction "2_2") (pintype "passive"))
    )
    (net (code "14") (name "GAIN_2") (class "Default")
      (node (ref "C18") (pin "1") (pinfunction "1_1") (pintype "passive"))
      (node (ref "IC10") (pin "14") (pinfunction "CTRL_14") (pintype "input"))
      (node (ref "R20") (pin "2") (pinfunction "2_2") (pintype "passive"))
    )
    (net (code "15") (name "GAIN_3") (class "Default")
      (node (ref "C19") (pin "1") (pinfunction "1_1") (pintype "passive"))
      (node (ref "IC10") (pin "11") (pinfunction "CTRL_11") (pintype "input"))
      (node (ref "R21") (pin "2") (pinfunction "2_2") (pintype "passive"))
    )
    (net (code "16") (name "GAIN_4") (class "Default")
      (node (ref "C20") (pin "1") (pinfunction "1_1") (pintype "passive"))
      (node (ref "IC10") (pin "6") (pinfunction "CTRL_6") (pintype "input"))
      (node (ref "R22") (pin "2") (pinfunction "2_2") (pintype "passive"))
    )
    (net (code "17") (name "GND") (class "Default")
      (node (ref "C1") (pin "1") (pinfunction "1_1") (pintype "passive"))
      (node (ref "C10") (pin "2") (pinfunction "2_2") (pintype "passive"))
      (node (ref "C11") (pin "-") (pinfunction "-_-") (pintype "passive"))
      (node (ref "C12") (pin "2") (pinfunction "2_2") (pintype "passive"))
      (node (ref "C13") (pin "2") (pinfunction "2_2") (pintype "passive"))
      (node (ref "C14") (pin "2") (pinfunction "2_2") (pintype "passive"))
      (node (ref "C15") (pin "-") (pinfunction "-_-") (pintype "passive"))
      (node (ref "C16") (pin "2") (pinfunction "2_2") (pintype "passive"))
      (node (ref "C17") (pin "2") (pinfunction "2_2") (pintype "passive"))
      (node (ref "C18") (pin "2") (pinfunction "2_2") (pintype "passive"))
      (node (ref "C19") (pin "2") (pinfunction "2_2") (pintype "passive"))
      (node (ref "C2") (pin "2") (pinfunction "2_2") (pintype "passive"))
      (node (ref "C20") (pin "2") (pinfunction "2_2") (pintype "passive"))
      (node (ref "C21") (pin "+") (pinfunction "+_+") (pintype "passive"))
      (node (ref "C22") (pin "2") (pinfunction "2_2") (pintype "passive"))
      (node (ref "C24") (pin "2") (pinfunction "2_2") (pintype "passive"))
      (node (ref "C25") (pin "2") (pinfunction "2_2") (pintype "passive"))
      (node (ref "C26") (pin "2") (pinfunction "2_2") (pintype "passive"))
      (node (ref "C27") (pin "2") (pinfunction "2_2") (pintype "passive"))
      (node (ref "C28") (pin "1") (pinfunction "1_1") (pintype "passive"))
      (node (ref "C29") (pin "2") (pinfunction "2_2") (pintype "passive"))
      (node (ref "C3") (pin "2") (pinfunction "2_2") (pintype "passive"))
      (node (ref "C30") (pin "2") (pinfunction "2_2") (pintype "passive"))
      (node (ref "C34") (pin "2") (pinfunction "2_2") (pintype "passive"))
      (node (ref "C35") (pin "2") (pinfunction "2_2") (pintype "passive"))
      (node (ref "C36") (pin "1") (pinfunction "1_1") (pintype "passive"))
      (node (ref "C37") (pin "1") (pinfunction "1_1") (pintype "passive"))
      (node (ref "C4") (pin "-") (pinfunction "-_-") (pintype "passive"))
      (node (ref "C41") (pin "1") (pinfunction "1_1") (pintype "passive"))
      (node (ref "C42") (pin "2") (pinfunction "2_2") (pintype "passive"))
      (node (ref "C43") (pin "2") (pinfunction "2_2") (pintype "passive"))
      (node (ref "C45") (pin "1") (pinfunction "1_1") (pintype "passive"))
      (node (ref "C47") (pin "1") (pinfunction "1_1") (pintype "passive"))
      (node (ref "C48") (pin "1") (pinfunction "1_1") (pintype "passive"))
      (node (ref "C5") (pin "-") (pinfunction "-_-") (pintype "passive"))
      (node (ref "C6") (pin "2") (pinfunction "2_2") (pintype "passive"))
      (node (ref "C7") (pin "2") (pinfunction "2_2") (pintype "passive"))
      (node (ref "C8") (pin "2") (pinfunction "2_2") (pintype "passive"))
      (node (ref "C9") (pin "1") (pinfunction "1_1") (pintype "passive"))
      (node (ref "D1") (pin "A") (pinfunction "A_A") (pintype "passive"))
      (node (ref "D2") (pin "C") (pinfunction "C_C") (pintype "passive"))
      (node (ref "D3") (pin "1") (pinfunction "A_1") (pintype "passive"))
      (node (ref "IC1") (pin "1") (pinfunction "GND_1") (pintype "power_in"))
      (node (ref "IC10") (pin "8") (pinfunction "GND_8") (pintype "power_in"))
      (node (ref "IC11") (pin "3") (pinfunction "+IN_3") (pintype "input"))
      (node (ref "IC11") (pin "5") (pinfunction "+IN_5") (pintype "input"))
      (node (ref "IC12") (pin "3") (pinfunction "+IN_3") (pintype "input"))
      (node (ref "IC12") (pin "5") (pinfunction "+IN_5") (pintype "input"))
      (node (ref "IC13") (pin "3") (pinfunction "+IN_3") (pintype "input"))
      (node (ref "IC13") (pin "5") (pinfunction "+IN_5") (pintype "input"))
      (node (ref "IC2") (pin "2") (pinfunction "A_2") (pintype "passive"))
      (node (ref "IC3") (pin "6") (pinfunction "GND_6") (pintype "power_in"))
      (node (ref "IC4") (pin "1") (pinfunction "GND_1") (pintype "power_in"))
      (node (ref "IC5") (pin "2") (pinfunction "A_2") (pintype "passive"))
      (node (ref "IC7") (pin "3") (pinfunction "+IN_3") (pintype "input"))
      (node (ref "IC7") (pin "5") (pinfunction "+IN_5") (pintype "input"))
      (node (ref "IC8") (pin "3") (pinfunction "+IN_3") (pintype "input"))
      (node (ref "IC8") (pin "5") (pinfunction "+IN_5") (pintype "input"))
      (node (ref "IC9") (pin "3") (pinfunction "+IN_3") (pintype "input"))
      (node (ref "IC9") (pin "5") (pinfunction "+IN_5") (pintype "input"))
      (node (ref "J1") (pin "GND") (pinfunction "1_GND") (pintype "passive"))
      (node (ref "J1") (pin "GND2") (pinfunction "4_GND2") (pintype "passive"))
      (node (ref "J10") (pin "GND") (pinfunction "1_GND") (pintype "passive"))
      (node (ref "J10") (pin "GND2") (pinfunction "4_GND2") (pintype "passive"))
      (node (ref "J11") (pin "GND") (pinfunction "1_GND") (pintype "passive"))
      (node (ref "J11") (pin "GND2") (pinfunction "4_GND2") (pintype "passive"))
      (node (ref "J12") (pin "GND") (pinfunction "1_GND") (pintype "passive"))
      (node (ref "J12") (pin "GND2") (pinfunction "4_GND2") (pintype "passive"))
      (node (ref "J2") (pin "GND") (pinfunction "1_GND") (pintype "passive"))
      (node (ref "J2") (pin "GND2") (pinfunction "4_GND2") (pintype "passive"))
      (node (ref "J3") (pin "GND") (pinfunction "1_GND") (pintype "passive"))
      (node (ref "J3") (pin "GND2") (pinfunction "4_GND2") (pintype "passive"))
      (node (ref "J4") (pin "GND") (pinfunction "1_GND") (pintype "passive"))
      (node (ref "J4") (pin "GND2") (pinfunction "4_GND2") (pintype "passive"))
      (node (ref "J5") (pin "GND") (pinfunction "1_GND") (pintype "passive"))
      (node (ref "J5") (pin "GND2") (pinfunction "4_GND2") (pintype "passive"))
      (node (ref "J6") (pin "GND") (pinfunction "1_GND") (pintype "passive"))
      (node (ref "J6") (pin "GND2") (pinfunction "4_GND2") (pintype "passive"))
      (node (ref "J7") (pin "GND") (pinfunction "1_GND") (pintype "passive"))
      (node (ref "J7") (pin "GND2") (pinfunction "4_GND2") (pintype "passive"))
      (node (ref "J8") (pin "GND") (pinfunction "1_GND") (pintype "passive"))
      (node (ref "J8") (pin "GND2") (pinfunction "4_GND2") (pintype "passive"))
      (node (ref "J9") (pin "GND") (pinfunction "1_GND") (pintype "passive"))
      (node (ref "J9") (pin "GND2") (pinfunction "4_GND2") (pintype "passive"))
      (node (ref "JP2") (pin "3") (pinfunction "3_3") (pintype "passive"))
      (node (ref "JP2") (pin "4") (pinfunction "4_4") (pintype "passive"))
      (node (ref "JP2") (pin "5") (pinfunction "5_5") (pintype "passive"))
      (node (ref "JP2") (pin "6") (pinfunction "6_6") (pintype "passive"))
      (node (ref "JP2") (pin "7") (pinfunction "7_7") (pintype "passive"))
      (node (ref "JP2") (pin "8") (pinfunction "8_8") (pintype "passive"))
      (node (ref "JP3") (pin "1") (pinfunction "1_1") (pintype "passive"))
      (node (ref "JP4") (pin "3") (pinfunction "3_3") (pintype "passive"))
      (node (ref "JP4") (pin "5") (pinfunction "5_5") (pintype "passive"))
      (node (ref "JP4") (pin "9") (pinfunction "9_9") (pintype "passive"))
      (node (ref "LED1") (pin "K") (pinfunction "C_K") (pintype "passive"))
      (node (ref "LED2") (pin "K") (pinfunction "C_K") (pintype "passive"))
      (node (ref "LED3") (pin "K") (pinfunction "C_K") (pintype "passive"))
      (node (ref "LED4") (pin "K") (pinfunction "C_K") (pintype "passive"))
      (node (ref "LED5") (pin "GND") (pinfunction "C_GND") (pintype "bidirectional"))
      (node (ref "LED6") (pin "K") (pinfunction "C_K") (pintype "passive"))
      (node (ref "Q2") (pin "E") (pinfunction "E_E") (pintype "passive"))
      (node (ref "R1") (pin "1") (pinfunction "1_1") (pintype "passive"))
      (node (ref "R14") (pin "P$3") (pinfunction "A_P$3") (pintype "passive"))
      (node (ref "R2") (pin "P$3") (pinfunction "A_P$3") (pintype "passive"))
      (node (ref "R24") (pin "1") (pinfunction "1_1") (pintype "passive"))
      (node (ref "R3") (pin "P$3") (pinfunction "A_P$3") (pintype "passive"))
      (node (ref "R4") (pin "P$3") (pinfunction "A_P$3") (pintype "passive"))
      (node (ref "R5") (pin "P$3") (pinfunction "A_P$3") (pintype "passive"))
      (node (ref "R65") (pin "1") (pinfunction "1_1") (pintype "passive"))
      (node (ref "SW2") (pin "A") (pinfunction "P_A") (pintype "passive"))
      (node (ref "SW2") (pin "A'") (pinfunction "P1_A'") (pintype "passive"))
      (node (ref "SW3") (pin "B1") (pinfunction "P_B1") (pintype "passive"))
      (node (ref "SW3") (pin "B2") (pinfunction "P1_B2") (pintype "passive"))
      (node (ref "SW4") (pin "B1") (pinfunction "P_B1") (pintype "passive"))
      (node (ref "SW4") (pin "B2") (pinfunction "P1_B2") (pintype "passive"))
      (node (ref "SW5") (pin "O") (pinfunction "O_O") (pintype "passive"))
      (node (ref "UC1") (pin "20") (pinfunction "PB2/BOOT1_20") (pintype "bidirectional"))
      (node (ref "UC1") (pin "23") (pinfunction "VSS_1_23") (pintype "power_in"))
      (node (ref "UC1") (pin "35") (pinfunction "VSS_2_35") (pintype "power_in"))
      (node (ref "UC1") (pin "47") (pinfunction "VSS_3_47") (pintype "power_in"))
      (node (ref "UC1") (pin "8") (pinfunction "VSS_A_8") (pintype "power_in"))
    )
    (net (code "18") (name "IN_1") (class "Default")
      (node (ref "J2") (pin "TIP") (pinfunction "2_TIP") (pintype "passive"))
      (node (ref "R54") (pin "1") (pinfunction "1_1") (pintype "passive"))
    )
    (net (code "19") (name "IN_2") (class "Default")
      (node (ref "J3") (pin "TIP") (pinfunction "2_TIP") (pintype "passive"))
      (node (ref "R33") (pin "1") (pinfunction "1_1") (pintype "passive"))
    )
    (net (code "20") (name "IN_3") (class "Default")
      (node (ref "J4") (pin "TIP") (pinfunction "2_TIP") (pintype "passive"))
      (node (ref "R36") (pin "1") (pinfunction "1_1") (pintype "passive"))
    )
    (net (code "21") (name "IN_4") (class "Default")
      (node (ref "J5") (pin "TIP") (pinfunction "2_TIP") (pintype "passive"))
      (node (ref "R57") (pin "1") (pinfunction "1_1") (pintype "passive"))
    )
    (net (code "22") (name "JTCK") (class "Default")
      (node (ref "JP4") (pin "4") (pinfunction "4_4") (pintype "passive"))
      (node (ref "UC1") (pin "37") (pinfunction "PA14/JTCK/SWCLK_37") (pintype "bidirectional"))
    )
    (net (code "23") (name "JTDI") (class "Default")
      (node (ref "JP4") (pin "8") (pinfunction "8_8") (pintype "passive"))
      (node (ref "UC1") (pin "38") (pinfunction "PA15/JTDI_38") (pintype "bidirectional"))
    )
    (net (code "24") (name "JTDO") (class "Default")
      (node (ref "JP4") (pin "6") (pinfunction "6_6") (pintype "passive"))
      (node (ref "UC1") (pin "39") (pinfunction "PB3/JTDO_39") (pintype "bidirectional"))
    )
    (net (code "25") (name "JTMS") (class "Default")
      (node (ref "JP4") (pin "2") (pinfunction "2_2") (pintype "passive"))
      (node (ref "UC1") (pin "34") (pinfunction "PA13/JTMS/SWDIO_34") (pintype "bidirectional"))
    )
    (net (code "26") (name "LED_B") (class "Default")
      (node (ref "R12") (pin "1") (pinfunction "1_1") (pintype "passive"))
      (node (ref "UC1") (pin "18") (pinfunction "PB0/ADC12_IN8/TIM3_CH3_18") (pintype "bidirectional"))
    )
    (net (code "27") (name "LED_CH1") (class "Default")
      (node (ref "R6") (pin "1") (pinfunction "1_1") (pintype "passive"))
      (node (ref "UC1") (pin "46") (pinfunction "PB9/TIM4_CH4_46") (pintype "input"))
    )
    (net (code "28") (name "LED_CH2") (class "Default")
      (node (ref "R7") (pin "1") (pinfunction "1_1") (pintype "passive"))
      (node (ref "UC1") (pin "45") (pinfunction "PB8/TIM4_CH3_45") (pintype "bidirectional"))
    )
    (net (code "29") (name "LED_CH3") (class "Default")
      (node (ref "R8") (pin "1") (pinfunction "1_1") (pintype "passive"))
      (node (ref "UC1") (pin "43") (pinfunction "PB7/I2C1_SDA/TIM4_CH2_43") (pintype "bidirectional"))
    )
    (net (code "30") (name "LED_CH4") (class "Default")
      (node (ref "R9") (pin "1") (pinfunction "1_1") (pintype "passive"))
      (node (ref "UC1") (pin "42") (pinfunction "PB6/I2C1_SCL/TIM4_CH1_42") (pintype "input"))
    )
    (net (code "31") (name "LED_FRAME") (class "Default")
      (node (ref "R16") (pin "1") (pinfunction "1_1") (pintype "passive"))
      (node (ref "UC1") (pin "41") (pinfunction "PB5/I2C1_SMBA_41") (pintype "input"))
    )
    (net (code "32") (name "LED_G") (class "Default")
      (node (ref "R11") (pin "1") (pinfunction "1_1") (pintype "passive"))
      (node (ref "UC1") (pin "17") (pinfunction "PA7/SPI1_MOSI/ADC12_IN7/TIM3_CH2_17") (pintype "bidirectional"))
    )
    (net (code "33") (name "LED_R") (class "Default")
      (node (ref "R13") (pin "1") (pinfunction "1_1") (pintype "passive"))
      (node (ref "UC1") (pin "19") (pinfunction "PB1/ADC12_IN9/TIM3_CH4_19") (pintype "bidirectional"))
    )
    (net (code "34") (name "MODULATION") (class "Default")
      (node (ref "D3") (pin "3") (pinfunction "AC_3") (pintype "passive"))
      (node (ref "R39") (pin "1") (pinfunction "1_1") (pintype "passive"))
      (node (ref "UC1") (pin "14") (pinfunction "PA4/SPI1_NSS/USART2_CK/ADC12_IN4_14") (pintype "bidirectional"))
    )
    (net (code "35") (name "Net-(C22-Pad1)") (class "Default")
      (node (ref "C22") (pin "1") (pinfunction "1_1") (pintype "passive"))
      (node (ref "R34") (pin "1") (pinfunction "1_1") (pintype "passive"))
    )
    (net (code "36") (name "Net-(C27-Pad1)") (class "Default")
      (node (ref "C27") (pin "1") (pinfunction "1_1") (pintype "passive"))
      (node (ref "R35") (pin "1") (pinfunction "1_1") (pintype "passive"))
    )
    (net (code "37") (name "Net-(C42-Pad1)") (class "Default")
      (node (ref "C42") (pin "1") (pinfunction "1_1") (pintype "passive"))
      (node (ref "R55") (pin "1") (pinfunction "1_1") (pintype "passive"))
    )
    (net (code "38") (name "Net-(C43-Pad1)") (class "Default")
      (node (ref "C43") (pin "1") (pinfunction "1_1") (pintype "passive"))
      (node (ref "R56") (pin "1") (pinfunction "1_1") (pintype "passive"))
    )
    (net (code "39") (name "Net-(IC3-OUTA)") (class "Default")
      (node (ref "IC3") (pin "2") (pinfunction "OUTA_2") (pintype "output"))
      (node (ref "R19") (pin "1") (pinfunction "1_1") (pintype "passive"))
    )
    (net (code "40") (name "Net-(IC3-OUTB)") (class "Default")
      (node (ref "IC3") (pin "3") (pinfunction "OUTB_3") (pintype "output"))
      (node (ref "R20") (pin "1") (pinfunction "1_1") (pintype "passive"))
    )
    (net (code "41") (name "Net-(IC3-OUTC)") (class "Default")
      (node (ref "IC3") (pin "4") (pinfunction "OUTC_4") (pintype "output"))
      (node (ref "R21") (pin "1") (pinfunction "1_1") (pintype "passive"))
    )
    (net (code "42") (name "Net-(IC3-OUTD)") (class "Default")
      (node (ref "IC3") (pin "5") (pinfunction "OUTD_5") (pintype "output"))
      (node (ref "R22") (pin "1") (pinfunction "1_1") (pintype "passive"))
    )
    (net (code "43") (name "Net-(IC5-C)") (class "Default")
      (node (ref "IC5") (pin "1") (pinfunction "C_1") (pintype "passive"))
      (node (ref "IC6") (pin "5") (pinfunction "+IN_5") (pintype "input"))
      (node (ref "R26") (pin "2") (pinfunction "2_2") (pintype "passive"))
      (node (ref "R27") (pin "2") (pinfunction "2_2") (pintype "passive"))
    )
    (net (code "44") (name "Net-(IC6A-+IN)") (class "Default")
      (node (ref "IC6") (pin "3") (pinfunction "+IN_3") (pintype "input"))
      (node (ref "R27") (pin "1") (pinfunction "1_1") (pintype "passive"))
      (node (ref "R65") (pin "2") (pinfunction "2_2") (pintype "passive"))
    )
    (net (code "45") (name "Net-(IC7A--IN)") (class "Default")
      (node (ref "C38") (pin "1") (pinfunction "1_1") (pintype "passive"))
      (node (ref "IC7") (pin "2") (pinfunction "-IN_2") (pintype "input"))
      (node (ref "R43") (pin "1") (pinfunction "1_1") (pintype "passive"))
      (node (ref "R44") (pin "2") (pinfunction "2_2") (pintype "passive"))
      (node (ref "R45") (pin "2") (pinfunction "2_2") (pintype "passive"))
      (node (ref "R46") (pin "2") (pinfunction "2_2") (pintype "passive"))
      (node (ref "R47") (pin "2") (pinfunction "2_2") (pintype "passive"))
    )
    (net (code "46") (name "Net-(IC7A-OUT)") (class "Default")
      (node (ref "C38") (pin "2") (pinfunction "2_2") (pintype "passive"))
      (node (ref "IC7") (pin "1") (pinfunction "OUT_1") (pintype "output"))
      (node (ref "R30") (pin "1") (pinfunction "1_1") (pintype "passive"))
      (node (ref "R43") (pin "2") (pinfunction "2_2") (pintype "passive"))
    )
    (net (code "47") (name "Net-(IC7B--IN)") (class "Default")
      (node (ref "C23") (pin "1") (pinfunction "1_1") (pintype "passive"))
      (node (ref "IC7") (pin "6") (pinfunction "-IN_6") (pintype "input"))
      (node (ref "R29") (pin "1") (pinfunction "1_1") (pintype "passive"))
      (node (ref "R30") (pin "2") (pinfunction "2_2") (pintype "passive"))
    )
    (net (code "48") (name "Net-(IC7B-OUT)") (class "Default")
      (node (ref "C23") (pin "2") (pinfunction "2_2") (pintype "passive"))
      (node (ref "IC7") (pin "7") (pinfunction "OUT_7") (pintype "output"))
      (node (ref "R28") (pin "1") (pinfunction "1_1") (pintype "passive"))
      (node (ref "R29") (pin "2") (pinfunction "2_2") (pintype "passive"))
    )
    (net (code "49") (name "Net-(IC8A--IN)") (class "Default")
      (node (ref "C39") (pin "1") (pinfunction "1_1") (pintype "passive"))
      (node (ref "IC8") (pin "2") (pinfunction "-IN_2") (pintype "input"))
      (node (ref "R49") (pin "1") (pinfunction "1_1") (pintype "passive"))
      (node (ref "R50") (pin "2") (pinfunction "2_2") (pintype "passive"))
    )
    (net (code "50") (name "Net-(IC8A-OUT)") (class "Default")
      (node (ref "C39") (pin "2") (pinfunction "2_2") (pintype "passive"))
      (node (ref "IC8") (pin "1") (pinfunction "OUT_1") (pintype "output"))
      (node (ref "R48") (pin "1") (pinfunction "1_1") (pintype "passive"))
      (node (ref "R49") (pin "2") (pinfunction "2_2") (pintype "passive"))
    )
    (net (code "51") (name "Net-(IC8B-OUT)") (class "Default")
      (node (ref "IC8") (pin "7") (pinfunction "OUT_7") (pintype "output"))
      (node (ref "R31") (pin "2") (pinfunction "2_2") (pintype "passive"))
      (node (ref "R50") (pin "1") (pinfunction "1_1") (pintype "passive"))
    )
    (net (code "52") (name "Net-(IC9A--IN)") (class "Default")
      (node (ref "C40") (pin "1") (pinfunction "1_1") (pintype "passive"))
      (node (ref "IC9") (pin "2") (pinfunction "-IN_2") (pintype "input"))
      (node (ref "R52") (pin "1") (pinfunction "1_1") (pintype "passive"))
      (node (ref "R53") (pin "2") (pinfunction "2_2") (pintype "passive"))
    )
    (net (code "53") (name "Net-(IC9A-OUT)") (class "Default")
      (node (ref "C40") (pin "2") (pinfunction "2_2") (pintype "passive"))
      (node (ref "IC9") (pin "1") (pinfunction "OUT_1") (pintype "output"))
      (node (ref "R51") (pin "1") (pinfunction "1_1") (pintype "passive"))
      (node (ref "R52") (pin "2") (pinfunction "2_2") (pintype "passive"))
    )
    (net (code "54") (name "Net-(IC9B-OUT)") (class "Default")
      (node (ref "IC9") (pin "7") (pinfunction "OUT_7") (pintype "output"))
      (node (ref "R32") (pin "2") (pinfunction "2_2") (pintype "passive"))
      (node (ref "R53") (pin "1") (pinfunction "1_1") (pintype "passive"))
    )
    (net (code "55") (name "Net-(IC10A-IN)") (class "Default")
      (node (ref "IC10") (pin "2") (pinfunction "IN_2") (pintype "input"))
      (node (ref "R54") (pin "2") (pinfunction "2_2") (pintype "passive"))
      (node (ref "R55") (pin "2") (pinfunction "2_2") (pintype "passive"))
    )
    (net (code "56") (name "Net-(IC10A-OUT)") (class "Default")
      (node (ref "IC10") (pin "4") (pinfunction "OUT_4") (pintype "output"))
      (node (ref "IC8") (pin "6") (pinfunction "-IN_6") (pintype "input"))
      (node (ref "R31") (pin "1") (pinfunction "1_1") (pintype "passive"))
    )
    (net (code "57") (name "Net-(IC10B-IN)") (class "Default")
      (node (ref "IC10") (pin "7") (pinfunction "IN_7") (pintype "input"))
      (node (ref "R56") (pin "2") (pinfunction "2_2") (pintype "passive"))
      (node (ref "R57") (pin "2") (pinfunction "2_2") (pintype "passive"))
    )
    (net (code "58") (name "Net-(IC10B-OUT)") (class "Default")
      (node (ref "IC10") (pin "5") (pinfunction "OUT_5") (pintype "output"))
      (node (ref "IC12") (pin "6") (pinfunction "-IN_6") (pintype "input"))
      (node (ref "R38") (pin "1") (pinfunction "1_1") (pintype "passive"))
    )
    (net (code "59") (name "Net-(IC10C-IN)") (class "Default")
      (node (ref "IC10") (pin "10") (pinfunction "IN_10") (pintype "input"))
      (node (ref "R35") (pin "2") (pinfunction "2_2") (pintype "passive"))
      (node (ref "R36") (pin "2") (pinfunction "2_2") (pintype "passive"))
    )
    (net (code "60") (name "Net-(IC10C-OUT)") (class "Default")
      (node (ref "IC10") (pin "12") (pinfunction "OUT_12") (pintype "output"))
      (node (ref "IC11") (pin "6") (pinfunction "-IN_6") (pintype "input"))
      (node (ref "R37") (pin "1") (pinfunction "1_1") (pintype "passive"))
    )
    (net (code "61") (name "Net-(IC10D-IN)") (class "Default")
      (node (ref "IC10") (pin "15") (pinfunction "IN_15") (pintype "input"))
      (node (ref "R33") (pin "2") (pinfunction "2_2") (pintype "passive"))
      (node (ref "R34") (pin "2") (pinfunction "2_2") (pintype "passive"))
    )
    (net (code "62") (name "Net-(IC10D-OUT)") (class "Default")
      (node (ref "IC10") (pin "13") (pinfunction "OUT_13") (pintype "output"))
      (node (ref "IC9") (pin "6") (pinfunction "-IN_6") (pintype "input"))
      (node (ref "R32") (pin "1") (pinfunction "1_1") (pintype "passive"))
    )
    (net (code "63") (name "Net-(IC11A--IN)") (class "Default")
      (node (ref "C44") (pin "1") (pinfunction "1_1") (pintype "passive"))
      (node (ref "IC11") (pin "2") (pinfunction "-IN_2") (pintype "input"))
      (node (ref "R59") (pin "1") (pinfunction "1_1") (pintype "passive"))
      (node (ref "R60") (pin "2") (pinfunction "2_2") (pintype "passive"))
    )
    (net (code "64") (name "Net-(IC11A-OUT)") (class "Default")
      (node (ref "C44") (pin "2") (pinfunction "2_2") (pintype "passive"))
      (node (ref "IC11") (pin "1") (pinfunction "OUT_1") (pintype "output"))
      (node (ref "R58") (pin "1") (pinfunction "1_1") (pintype "passive"))
      (node (ref "R59") (pin "2") (pinfunction "2_2") (pintype "passive"))
    )
    (net (code "65") (name "Net-(IC11B-OUT)") (class "Default")
      (node (ref "IC11") (pin "7") (pinfunction "OUT_7") (pintype "output"))
      (node (ref "R37") (pin "2") (pinfunction "2_2") (pintype "passive"))
      (node (ref "R60") (pin "1") (pinfunction "1_1") (pintype "passive"))
    )
    (net (code "66") (name "Net-(IC12A--IN)") (class "Default")
      (node (ref "C46") (pin "1") (pinfunction "1_1") (pintype "passive"))
      (node (ref "IC12") (pin "2") (pinfunction "-IN_2") (pintype "input"))
      (node (ref "R62") (pin "1") (pinfunction "1_1") (pintype "passive"))
      (node (ref "R63") (pin "2") (pinfunction "2_2") (pintype "passive"))
    )
    (net (code "67") (name "Net-(IC12A-OUT)") (class "Default")
      (node (ref "C46") (pin "2") (pinfunction "2_2") (pintype "passive"))
      (node (ref "IC12") (pin "1") (pinfunction "OUT_1") (pintype "output"))
      (node (ref "R61") (pin "1") (pinfunction "1_1") (pintype "passive"))
      (node (ref "R62") (pin "2") (pinfunction "2_2") (pintype "passive"))
    )
    (net (code "68") (name "Net-(IC12B-OUT)") (class "Default")
      (node (ref "IC12") (pin "7") (pinfunction "OUT_7") (pintype "output"))
      (node (ref "R38") (pin "2") (pinfunction "2_2") (pintype "passive"))
      (node (ref "R63") (pin "1") (pinfunction "1_1") (pintype "passive"))
    )
    (net (code "69") (name "Net-(IC13A--IN)") (class "Default")
      (node (ref "IC13") (pin "2") (pinfunction "-IN_2") (pintype "input"))
      (node (ref "R15") (pin "P$1") (pinfunction "E_P$1") (pintype "passive"))
      (node (ref "R64") (pin "2") (pinfunction "2_2") (pintype "passive"))
    )
    (net (code "70") (name "Net-(IC13A-OUT)") (class "Default")
      (node (ref "IC13") (pin "1") (pinfunction "OUT_1") (pintype "output"))
      (node (ref "R41") (pin "2") (pinfunction "2_2") (pintype "passive"))
      (node (ref "R64") (pin "1") (pinfunction "1_1") (pintype "passive"))
    )
    (net (code "71") (name "Net-(IC13B--IN)") (class "Default")
      (node (ref "C31") (pin "1") (pinfunction "1_1") (pintype "passive"))
      (node (ref "IC13") (pin "6") (pinfunction "-IN_6") (pintype "input"))
      (node (ref "R15") (pin "P$3") (pinfunction "A_P$3") (pintype "passive"))
      (node (ref "R40") (pin "2") (pinfunction "2_2") (pintype "passive"))
      (node (ref "R41") (pin "1") (pinfunction "1_1") (pintype "passive"))
      (node (ref "R42") (pin "1") (pinfunction "1_1") (pintype "passive"))
    )
    (net (code "72") (name "Net-(IC13B-OUT)") (class "Default")
      (node (ref "C31") (pin "2") (pinfunction "2_2") (pintype "passive"))
      (node (ref "IC13") (pin "7") (pinfunction "OUT_7") (pintype "output"))
      (node (ref "R39") (pin "2") (pinfunction "2_2") (pintype "passive"))
      (node (ref "R40") (pin "1") (pinfunction "1_1") (pintype "passive"))
    )
    (net (code "73") (name "Net-(J1-3)") (class "Default")
      (node (ref "J1") (pin "SW") (pinfunction "3_SW") (pintype "passive"))
      (node (ref "SW5") (pin "P") (pinfunction "P_P") (pintype "passive"))
    )
    (net (code "74") (name "Net-(J6-2)") (class "Default")
      (node (ref "J6") (pin "TIP") (pinfunction "2_TIP") (pintype "passive"))
      (node (ref "R18") (pin "1") (pinfunction "1_1") (pintype "passive"))
    )
    (net (code "75") (name "Net-(J7-2)") (class "Default")
      (node (ref "J7") (pin "TIP") (pinfunction "2_TIP") (pintype "passive"))
      (node (ref "R28") (pin "2") (pinfunction "2_2") (pintype "passive"))
    )
    (net (code "76") (name "Net-(J8-2)") (class "Default")
      (node (ref "J8") (pin "TIP") (pinfunction "2_TIP") (pintype "passive"))
      (node (ref "R48") (pin "2") (pinfunction "2_2") (pintype "passive"))
    )
    (net (code "77") (name "Net-(J9-2)") (class "Default")
      (node (ref "J9") (pin "TIP") (pinfunction "2_TIP") (pintype "passive"))
      (node (ref "R51") (pin "2") (pinfunction "2_2") (pintype "passive"))
    )
    (net (code "78") (name "Net-(J10-2)") (class "Default")
      (node (ref "J10") (pin "TIP") (pinfunction "2_TIP") (pintype "passive"))
      (node (ref "R58") (pin "2") (pinfunction "2_2") (pintype "passive"))
    )
    (net (code "79") (name "Net-(J11-2)") (class "Default")
      (node (ref "J11") (pin "TIP") (pinfunction "2_TIP") (pintype "passive"))
      (node (ref "R61") (pin "2") (pinfunction "2_2") (pintype "passive"))
    )
    (net (code "80") (name "Net-(J12-2)") (class "Default")
      (node (ref "J12") (pin "TIP") (pinfunction "2_TIP") (pintype "passive"))
      (node (ref "Q2") (pin "C") (pinfunction "C_C") (pintype "passive"))
      (node (ref "R24") (pin "2") (pinfunction "2_2") (pintype "passive"))
      (node (ref "R25") (pin "1") (pinfunction "1_1") (pintype "passive"))
    )
    (net (code "81") (name "Net-(JP1-Pad2)") (class "Default")
      (node (ref "JP1") (pin "2") (pinfunction "2_2") (pintype "passive"))
      (node (ref "SW5") (pin "S") (pinfunction "S_S") (pintype "passive"))
    )
    (net (code "82") (name "Net-(JP2-Pad1)") (class "Default")
      (node (ref "JP2") (pin "1") (pinfunction "1_1") (pintype "passive"))
      (node (ref "JP2") (pin "2") (pinfunction "2_2") (pintype "passive"))
      (node (ref "P1") (pin "2") (pinfunction "2_2") (pintype "bidirectional"))
    )
    (net (code "83") (name "Net-(JP2-Pad10)") (class "Default")
      (node (ref "JP2") (pin "10") (pinfunction "10_10") (pintype "passive"))
      (node (ref "JP2") (pin "9") (pinfunction "9_9") (pintype "passive"))
      (node (ref "P2") (pin "2") (pinfunction "2_2") (pintype "bidirectional"))
    )
    (net (code "84") (name "Net-(LED1-PadA)") (class "Default")
      (node (ref "LED1") (pin "A") (pinfunction "A_A") (pintype "passive"))
      (node (ref "R6") (pin "2") (pinfunction "2_2") (pintype "passive"))
    )
    (net (code "85") (name "Net-(LED2-PadA)") (class "Default")
      (node (ref "LED2") (pin "A") (pinfunction "A_A") (pintype "passive"))
      (node (ref "R7") (pin "2") (pinfunction "2_2") (pintype "passive"))
    )
    (net (code "86") (name "Net-(LED3-PadA)") (class "Default")
      (node (ref "LED3") (pin "A") (pinfunction "A_A") (pintype "passive"))
      (node (ref "R8") (pin "2") (pinfunction "2_2") (pintype "passive"))
    )
    (net (code "87") (name "Net-(LED4-PadA)") (class "Default")
      (node (ref "LED4") (pin "A") (pinfunction "A_A") (pintype "passive"))
      (node (ref "R9") (pin "2") (pinfunction "2_2") (pintype "passive"))
    )
    (net (code "88") (name "Net-(LED5-PadBLU)") (class "Default")
      (node (ref "LED5") (pin "BLU") (pinfunction "BLU_BLU") (pintype "bidirectional"))
      (node (ref "R12") (pin "2") (pinfunction "2_2") (pintype "passive"))
    )
    (net (code "89") (name "Net-(LED5-PadGRN)") (class "Default")
      (node (ref "LED5") (pin "GRN") (pinfunction "GRN_GRN") (pintype "bidirectional"))
      (node (ref "R11") (pin "2") (pinfunction "2_2") (pintype "passive"))
    )
    (net (code "90") (name "Net-(LED5-PadRED)") (class "Default")
      (node (ref "LED5") (pin "RED") (pinfunction "RED_RED") (pintype "bidirectional"))
      (node (ref "R13") (pin "2") (pinfunction "2_2") (pintype "passive"))
    )
    (net (code "91") (name "Net-(LED6-PadA)") (class "Default")
      (node (ref "LED6") (pin "A") (pinfunction "A_A") (pintype "passive"))
      (node (ref "R16") (pin "2") (pinfunction "2_2") (pintype "passive"))
    )
    (net (code "92") (name "Net-(Q2-PadB)") (class "Default")
      (node (ref "Q2") (pin "B") (pinfunction "B_B") (pintype "passive"))
      (node (ref "R23") (pin "2") (pinfunction "2_2") (pintype "passive"))
    )
    (net (code "93") (name "Net-(R15-S)") (class "Default")
      (node (ref "R15") (pin "P$2") (pinfunction "S_P$2") (pintype "passive"))
      (node (ref "R18") (pin "2") (pinfunction "2_2") (pintype "passive"))
    )
    (net (code "94") (name "Net-(UC1-PD0-OSC_IN)") (class "Default")
      (node (ref "C1") (pin "2") (pinfunction "2_2") (pintype "passive"))
      (node (ref "Q1") (pin "2") (pinfunction "2_2") (pintype "passive"))
      (node (ref "UC1") (pin "5") (pinfunction "PD0-OSC_IN_5") (pintype "input"))
    )
    (net (code "95") (name "Net-(UC1-PD1-OSC_OUT)") (class "Default")
      (node (ref "C9") (pin "2") (pinfunction "2_2") (pintype "passive"))
      (node (ref "Q1") (pin "1") (pinfunction "1_1") (pintype "passive"))
      (node (ref "UC1") (pin "6") (pinfunction "PD1-OSC_OUT_6") (pintype "input"))
    )
    (net (code "96") (name "PAN") (class "Default")
      (node (ref "J1") (pin "TIP") (pinfunction "2_TIP") (pintype "passive"))
      (node (ref "J2") (pin "SW") (pinfunction "3_SW") (pintype "passive"))
      (node (ref "J3") (pin "SW") (pinfunction "3_SW") (pintype "passive"))
      (node (ref "J4") (pin "SW") (pinfunction "3_SW") (pintype "passive"))
      (node (ref "J5") (pin "SW") (pinfunction "3_SW") (pintype "passive"))
    )
    (net (code "97") (name "POT_CH1") (class "Default")
      (node (ref "R2") (pin "P$2") (pinfunction "S_P$2") (pintype "passive"))
      (node (ref "UC1") (pin "10") (pinfunction "PA0_WKUP/USART2_CTS/ADC12_IN0/TIM2_CH1_ETR_10") (pintype "bidirectional"))
    )
    (net (code "98") (name "POT_CH2") (class "Default")
      (node (ref "R3") (pin "P$2") (pinfunction "S_P$2") (pintype "passive"))
      (node (ref "UC1") (pin "11") (pinfunction "PA1/USART2_RTS/ADC12_IN1/TIM2_CH2_11") (pintype "bidirectional"))
    )
    (net (code "99") (name "POT_CH3") (class "Default")
      (node (ref "R4") (pin "P$2") (pinfunction "S_P$2") (pintype "passive"))
      (node (ref "UC1") (pin "12") (pinfunction "PA2/USART2_TX/ADC12_IN2/TIM2_CH3_12") (pintype "bidirectional"))
    )
    (net (code "100") (name "POT_CH4") (class "Default")
      (node (ref "R5") (pin "P$2") (pinfunction "S_P$2") (pintype "passive"))
      (node (ref "UC1") (pin "13") (pinfunction "PA3/USART2_RX/ADC12_IN3/TIM2_CH4_13") (pintype "bidirectional"))
    )
    (net (code "101") (name "POT_FRAME") (class "Default")
      (node (ref "R14") (pin "P$2") (pinfunction "S_P$2") (pintype "passive"))
      (node (ref "UC1") (pin "15") (pinfunction "PA5/SPI1_SCK/ADC12_IN5_15") (pintype "bidirectional"))
    )
    (net (code "102") (name "RESET") (class "Default")
      (node (ref "JP4") (pin "10") (pinfunction "10_10") (pintype "passive"))
      (node (ref "R10") (pin "1") (pinfunction "1_1") (pintype "passive"))
      (node (ref "SW2") (pin "B") (pinfunction "S_B") (pintype "passive"))
      (node (ref "SW2") (pin "B'") (pinfunction "S1_B'") (pintype "passive"))
      (node (ref "UC1") (pin "7") (pinfunction "NRST_7") (pintype "input"))
    )
    (net (code "103") (name "RX") (class "Default")
      (node (ref "JP3") (pin "4") (pinfunction "4_4") (pintype "passive"))
      (node (ref "UC1") (pin "31") (pinfunction "PA10/USART1_RX/TIM1_CH3_31") (pintype "bidirectional"))
    )
    (net (code "104") (name "TX") (class "Default")
      (node (ref "JP3") (pin "5") (pinfunction "5_5") (pintype "passive"))
      (node (ref "UC1") (pin "30") (pinfunction "PA9/USART1_TX/TIM1_CH2_30") (pintype "input"))
    )
    (net (code "105") (name "VCA_1") (class "Default")
      (node (ref "J8") (pin "SW") (pinfunction "3_SW") (pintype "passive"))
      (node (ref "R44") (pin "1") (pinfunction "1_1") (pintype "passive"))
    )
    (net (code "106") (name "VCA_2") (class "Default")
      (node (ref "J9") (pin "SW") (pinfunction "3_SW") (pintype "passive"))
      (node (ref "R47") (pin "1") (pinfunction "1_1") (pintype "passive"))
    )
    (net (code "107") (name "VCA_3") (class "Default")
      (node (ref "J10") (pin "SW") (pinfunction "3_SW") (pintype "passive"))
      (node (ref "R46") (pin "1") (pinfunction "1_1") (pintype "passive"))
    )
    (net (code "108") (name "VCA_4") (class "Default")
      (node (ref "J11") (pin "SW") (pinfunction "3_SW") (pintype "passive"))
      (node (ref "R45") (pin "1") (pinfunction "1_1") (pintype "passive"))
    )
    (net (code "109") (name "VCC") (class "Default")
      (node (ref "C11") (pin "+") (pinfunction "+_+") (pintype "passive"))
      (node (ref "C24") (pin "1") (pinfunction "1_1") (pintype "passive"))
      (node (ref "C25") (pin "1") (pinfunction "1_1") (pintype "passive"))
      (node (ref "C26") (pin "1") (pinfunction "1_1") (pintype "passive"))
      (node (ref "C29") (pin "1") (pinfunction "1_1") (pintype "passive"))
      (node (ref "C30") (pin "1") (pinfunction "1_1") (pintype "passive"))
      (node (ref "C34") (pin "1") (pinfunction "1_1") (pintype "passive"))
      (node (ref "C35") (pin "1") (pinfunction "1_1") (pintype "passive"))
      (node (ref "C4") (pin "+") (pinfunction "+_+") (pintype "passive"))
      (node (ref "D1") (pin "C") (pinfunction "C_C") (pintype "passive"))
      (node (ref "IC1") (pin "3") (pinfunction "VIN_3") (pintype "input"))
      (node (ref "IC10") (pin "16") (pinfunction "V+_16") (pintype "power_in"))
      (node (ref "IC11") (pin "8") (pinfunction "V+_8") (pintype "power_in"))
      (node (ref "IC12") (pin "8") (pinfunction "V+_8") (pintype "power_in"))
      (node (ref "IC13") (pin "8") (pinfunction "V+_8") (pintype "power_in"))
      (node (ref "IC4") (pin "3") (pinfunction "VIN_3") (pintype "input"))
      (node (ref "IC6") (pin "8") (pinfunction "V+_8") (pintype "power_in"))
      (node (ref "IC7") (pin "8") (pinfunction "V+_8") (pintype "power_in"))
      (node (ref "IC8") (pin "8") (pinfunction "V+_8") (pintype "power_in"))
      (node (ref "IC9") (pin "8") (pinfunction "V+_8") (pintype "power_in"))
      (node (ref "P1") (pin "1") (pinfunction "1_1") (pintype "bidirectional"))
      (node (ref "R25") (pin "2") (pinfunction "2_2") (pintype "passive"))
      (node (ref "R26") (pin "1") (pinfunction "1_1") (pintype "passive"))
    )
    (net (code "110") (name "VEE") (class "Default")
      (node (ref "C21") (pin "-") (pinfunction "-_-") (pintype "passive"))
      (node (ref "C28") (pin "2") (pinfunction "2_2") (pintype "passive"))
      (node (ref "C36") (pin "2") (pinfunction "2_2") (pintype "passive"))
      (node (ref "C37") (pin "2") (pinfunction "2_2") (pintype "passive"))
      (node (ref "C41") (pin "2") (pinfunction "2_2") (pintype "passive"))
      (node (ref "C45") (pin "2") (pinfunction "2_2") (pintype "passive"))
      (node (ref "C47") (pin "2") (pinfunction "2_2") (pintype "passive"))
      (node (ref "C48") (pin "2") (pinfunction "2_2") (pintype "passive"))
      (node (ref "D2") (pin "A") (pinfunction "A_A") (pintype "passive"))
      (node (ref "IC10") (pin "9") (pinfunction "V-_9") (pintype "power_in"))
      (node (ref "IC11") (pin "4") (pinfunction "V-_4") (pintype "power_in"))
      (node (ref "IC12") (pin "4") (pinfunction "V-_4") (pintype "power_in"))
      (node (ref "IC13") (pin "4") (pinfunction "V-_4") (pintype "power_in"))
      (node (ref "IC6") (pin "4") (pinfunction "V-_4") (pintype "power_in"))
      (node (ref "IC7") (pin "4") (pinfunction "V-_4") (pintype "power_in"))
      (node (ref "IC8") (pin "4") (pinfunction "V-_4") (pintype "power_in"))
      (node (ref "IC9") (pin "4") (pinfunction "V-_4") (pintype "power_in"))
      (node (ref "P2") (pin "1") (pinfunction "1_1") (pintype "bidirectional"))
      (node (ref "R42") (pin "2") (pinfunction "2_2") (pintype "passive"))
    )
    (net (code "111") (name "unconnected-(IC10E-MODE-Pad1)") (class "Default")
      (node (ref "IC10") (pin "1") (pinfunction "MODE_1") (pintype "input"))
    )
    (net (code "112") (name "unconnected-(J6-3-PadSW)") (class "Default")
      (node (ref "J6") (pin "SW") (pinfunction "3_SW") (pintype "passive"))
    )
    (net (code "113") (name "unconnected-(J7-3-PadSW)") (class "Default")
      (node (ref "J7") (pin "SW") (pinfunction "3_SW") (pintype "passive"))
    )
    (net (code "114") (name "unconnected-(J12-3-PadSW)") (class "Default")
      (node (ref "J12") (pin "SW") (pinfunction "3_SW") (pintype "passive"))
    )
    (net (code "115") (name "unconnected-(JP3-Pad2)") (class "Default")
      (node (ref "JP3") (pin "2") (pinfunction "2_2") (pintype "passive"))
    )
    (net (code "116") (name "unconnected-(JP3-Pad3)") (class "Default")
      (node (ref "JP3") (pin "3") (pinfunction "3_3") (pintype "passive"))
    )
    (net (code "117") (name "unconnected-(JP3-Pad6)") (class "Default")
      (node (ref "JP3") (pin "6") (pinfunction "6_6") (pintype "passive"))
    )
    (net (code "118") (name "unconnected-(JP4-Pad7)") (class "Default")
      (node (ref "JP4") (pin "7") (pinfunction "7_7") (pintype "passive"))
    )
    (net (code "119") (name "unconnected-(UC1-PA8{slash}USART1_CK{slash}TIM1_CH1{slash}MCO-Pad29)") (class "Default")
      (node (ref "UC1") (pin "29") (pinfunction "PA8/USART1_CK/TIM1_CH1/MCO_29") (pintype "bidirectional"))
    )
    (net (code "120") (name "unconnected-(UC1-PA11{slash}USART1_CTS{slash}CAN_RX{slash}TIM1_CH4{slash}USBDM-Pad32)") (class "Default")
      (node (ref "UC1") (pin "32") (pinfunction "PA11/USART1_CTS/CAN_RX/TIM1_CH4/USBDM_32") (pintype "bidirectional"))
    )
    (net (code "121") (name "unconnected-(UC1-PA12{slash}USART1_RTS{slash}CAN_TX{slash}TIM1_ETR{slash}USBDP-Pad33)") (class "Default")
      (node (ref "UC1") (pin "33") (pinfunction "PA12/USART1_RTS/CAN_TX/TIM1_ETR/USBDP_33") (pintype "bidirectional"))
    )
    (net (code "122") (name "unconnected-(UC1-PB4{slash}NJTRST-Pad40)") (class "Default")
      (node (ref "UC1") (pin "40") (pinfunction "PB4/NJTRST_40") (pintype "bidirectional"))
    )
    (net (code "123") (name "unconnected-(UC1-PB14{slash}SPI2_MISO{slash}USART3_RTS{slash}TIM1_CH2N-Pad27)") (class "Default")
      (node (ref "UC1") (pin "27") (pinfunction "PB14/SPI2_MISO/USART3_RTS/TIM1_CH2N_27") (pintype "input"))
    )
    (net (code "124") (name "unconnected-(UC1-PC13-TAMPER-RTC-Pad2)") (class "Default")
      (node (ref "UC1") (pin "2") (pinfunction "PC13-TAMPER-RTC_2") (pintype "input"))
    )
    (net (code "125") (name "unconnected-(UC1-PC14-OSC32_IN-Pad3)") (class "Default")
      (node (ref "UC1") (pin "3") (pinfunction "PC14-OSC32_IN_3") (pintype "input"))
    )
    (net (code "126") (name "unconnected-(UC1-PC15-OSC32_OUT-Pad4)") (class "Default")
      (node (ref "UC1") (pin "4") (pinfunction "PC15-OSC32_OUT_4") (pintype "input"))
    )
  )
)
